# Isolated_Oscilloscope_Diferential_Probe.net
KiCad netlist of a schematic drawn in Altium Designer
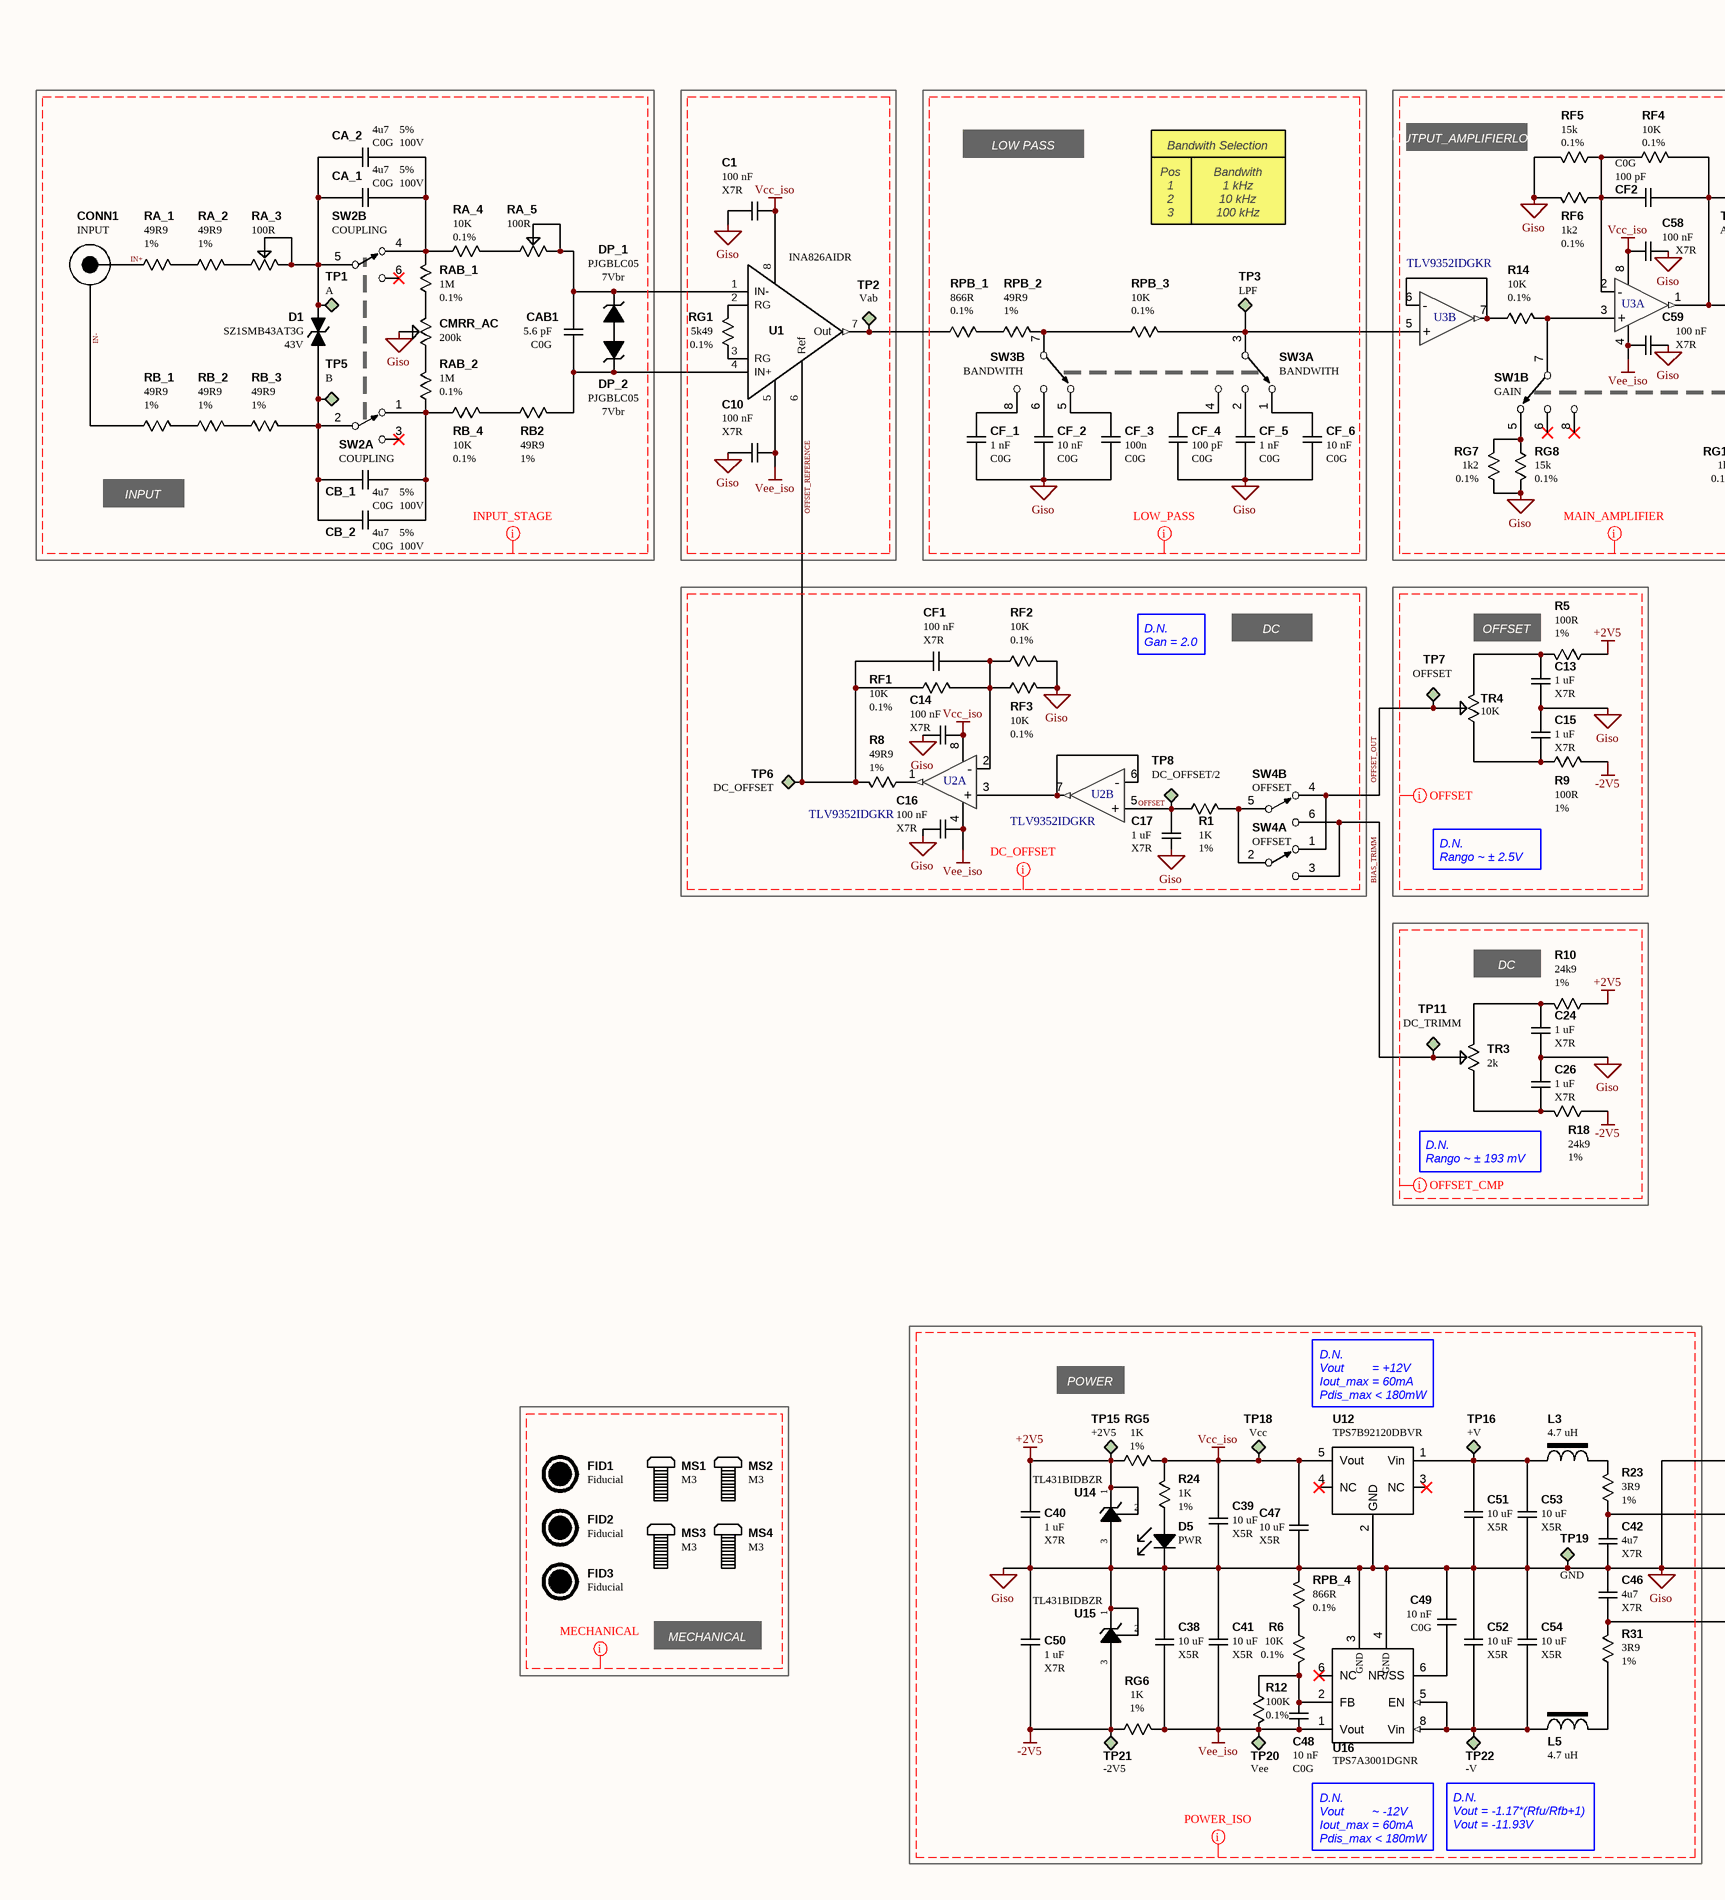
[diagram p0: Isolated_Oscilloscope_Diferential_Probe.SchDoc, left]
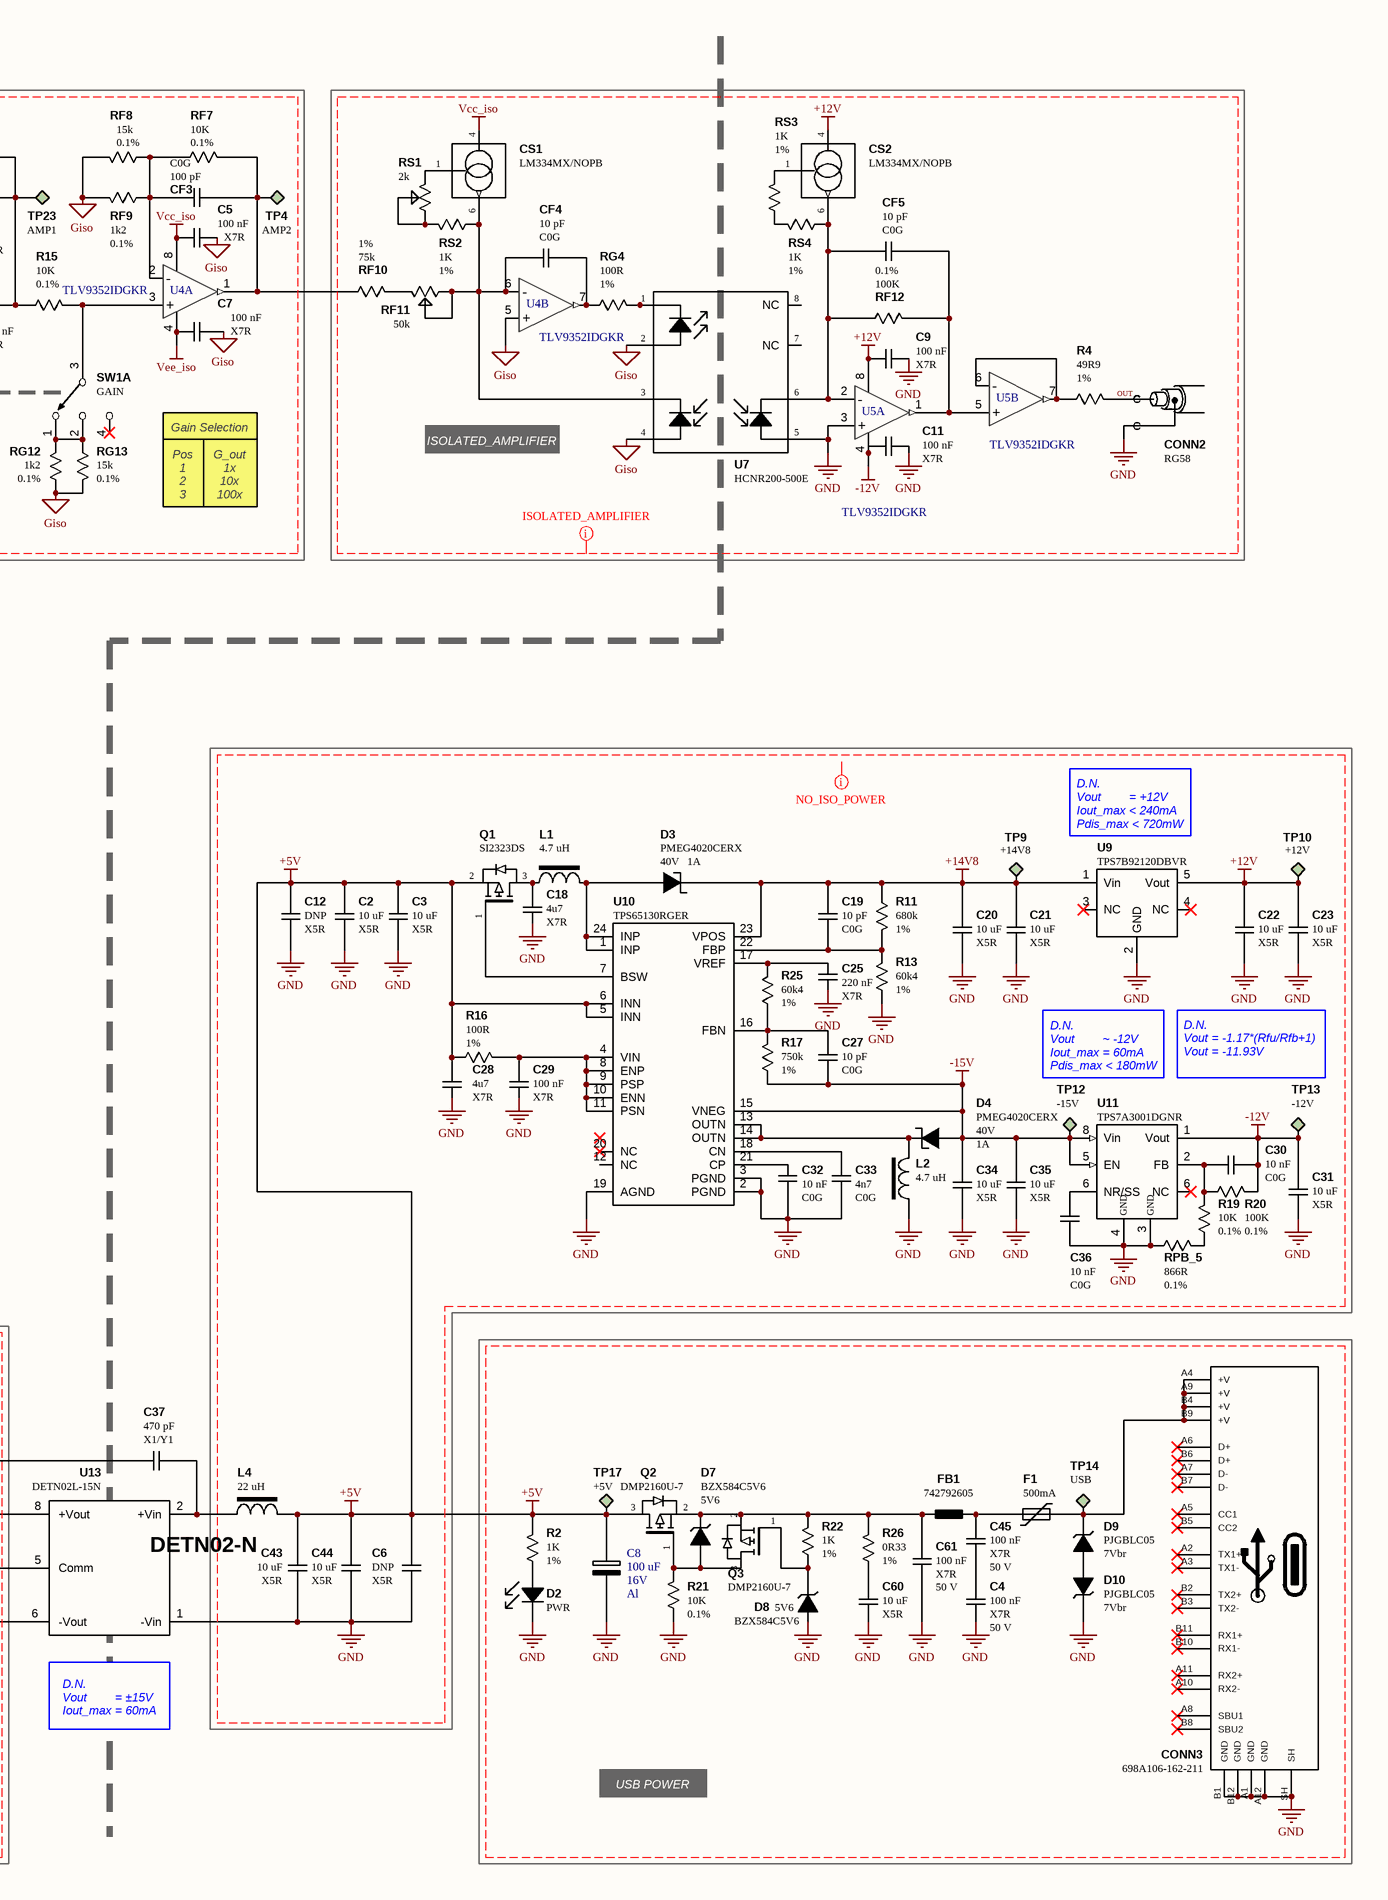
[diagram p1: Isolated_Oscilloscope_Diferential_Probe.SchDoc, right]

(export (version "E")
  (design (tool "Eeschema 10.0.6"))
  (components
    (comp (ref "C1")
      (value "100 nF")
      (footprint "CAP_SMD_0603")
      (description "0.1 µF ±10% 50V Ceramic Capacitor X7R 0603 (1608 Metric)")
      (fields
        (field (name "04_MANUFACTURER PART NUMBER") "CC0603KRX7R9BB104")
        (field (name "05_DIGIKEY PART NUMBER") "311-1344-1-ND")
        (field (name "DIELECTRICO") "X7R")
      )
      (libsource (lib "Libreria_Altium") (part "Capacitor NP"))
    )
    (comp (ref "C2")
      (value "10 uF")
      (footprint "CAP_SMD_0805")
      (description "10 µF ±10% 50V Ceramic Capacitor X5R 0805 (2012 Metric)")
      (fields
        (field (name "04_MANUFACTURER PART NUMBER") "GRM21BR61H106KE43L")
        (field (name "05_DIGIKEY PART NUMBER") "490-18663-1-ND")
        (field (name "DIELECTRICO") "X5R")
      )
      (libsource (lib "Libreria_Altium") (part "Capacitor NP"))
    )
    (comp (ref "C3")
      (value "10 uF")
      (footprint "CAP_SMD_0805")
      (description "10 µF ±10% 50V Ceramic Capacitor X5R 0805 (2012 Metric)")
      (fields
        (field (name "04_MANUFACTURER PART NUMBER") "GRM21BR61H106KE43L")
        (field (name "05_DIGIKEY PART NUMBER") "490-18663-1-ND")
        (field (name "DIELECTRICO") "X5R")
      )
      (libsource (lib "Libreria_Altium") (part "Capacitor NP"))
    )
    (comp (ref "C4")
      (value "100 nF")
      (footprint "CAP_SMD_0603")
      (description "0.1 µF ±10% 50V Ceramic Capacitor X7R 0603 (1608 Metric)")
      (fields
        (field (name "04_MANUFACTURER PART NUMBER") "CC0603KRX7R9BB104")
        (field (name "05_DIGIKEY PART NUMBER") "311-1344-1-ND")
        (field (name "TENSIÓN") "50 V")
        (field (name "DIELECTRICO") "X7R")
      )
      (libsource (lib "Libreria_Altium") (part "Capacitor NP"))
    )
    (comp (ref "C5")
      (value "100 nF")
      (footprint "CAP_SMD_0603")
      (description "0.1 µF ±10% 50V Ceramic Capacitor X7R 0603 (1608 Metric)")
      (fields
        (field (name "04_MANUFACTURER PART NUMBER") "CC0603KRX7R9BB104")
        (field (name "05_DIGIKEY PART NUMBER") "311-1344-1-ND")
        (field (name "DIELECTRICO") "X7R")
      )
      (libsource (lib "Libreria_Altium") (part "Capacitor NP"))
    )
    (comp (ref "C6")
      (value "DNP")
      (footprint "CAP_SMD_0805")
      (description "10 µF ±10% 50V Ceramic Capacitor X5R 0805 (2012 Metric)")
      (fields
        (field (name "04_MANUFACTURER PART NUMBER") "GRM21BR61H106KE43L")
        (field (name "05_DIGIKEY PART NUMBER") "490-18663-1-ND")
        (field (name "DIELECTRICO") "X5R")
      )
      (libsource (lib "Libreria_Altium") (part "Capacitor NP"))
    )
    (comp (ref "C7")
      (value "100 nF")
      (footprint "CAP_SMD_0603")
      (description "0.1 µF ±10% 50V Ceramic Capacitor X7R 0603 (1608 Metric)")
      (fields
        (field (name "04_MANUFACTURER PART NUMBER") "CC0603KRX7R9BB104")
        (field (name "05_DIGIKEY PART NUMBER") "311-1344-1-ND")
        (field (name "DIELECTRICO") "X7R")
      )
      (libsource (lib "Libreria_Altium") (part "Capacitor NP"))
    )
    (comp (ref "C8")
      (value "100 uF")
      (footprint "CAP_SMD_RADIAL_6.3mm")
      (fields
        (field (name "04_MANUFACTURER PART NUMBER") "875105344010")
        (field (name "05_DIGIKEY PART NUMBER") "732-6425-1-ND")
        (field (name "TENSIÓN") "16V")
        (field (name "DIELECTRICO") "Al")
      )
      (libsource (lib "03_Componentes Pasivos") (part "Capacitor Polarizado"))
    )
    (comp (ref "C9")
      (value "100 nF")
      (footprint "CAP_SMD_0603")
      (description "0.1 µF ±10% 50V Ceramic Capacitor X7R 0603 (1608 Metric)")
      (fields
        (field (name "04_MANUFACTURER PART NUMBER") "CC0603KRX7R9BB104")
        (field (name "05_DIGIKEY PART NUMBER") "311-1344-1-ND")
        (field (name "DIELECTRICO") "X7R")
      )
      (libsource (lib "Libreria_Altium") (part "Capacitor NP"))
    )
    (comp (ref "C10")
      (value "100 nF")
      (footprint "CAP_SMD_0603")
      (description "0.1 µF ±10% 50V Ceramic Capacitor X7R 0603 (1608 Metric)")
      (fields
        (field (name "04_MANUFACTURER PART NUMBER") "CC0603KRX7R9BB104")
        (field (name "05_DIGIKEY PART NUMBER") "311-1344-1-ND")
        (field (name "DIELECTRICO") "X7R")
      )
      (libsource (lib "Libreria_Altium") (part "Capacitor NP"))
    )
    (comp (ref "C11")
      (value "100 nF")
      (footprint "CAP_SMD_0603")
      (description "0.1 µF ±10% 50V Ceramic Capacitor X7R 0603 (1608 Metric)")
      (fields
        (field (name "04_MANUFACTURER PART NUMBER") "CC0603KRX7R9BB104")
        (field (name "05_DIGIKEY PART NUMBER") "311-1344-1-ND")
        (field (name "DIELECTRICO") "X7R")
      )
      (libsource (lib "Libreria_Altium") (part "Capacitor NP"))
    )
    (comp (ref "C12")
      (value "DNP")
      (footprint "CAP_SMD_0805")
      (description "10 µF ±10% 50V Ceramic Capacitor X5R 0805 (2012 Metric)")
      (fields
        (field (name "04_MANUFACTURER PART NUMBER") "GRM21BR61H106KE43L")
        (field (name "05_DIGIKEY PART NUMBER") "490-18663-1-ND")
        (field (name "DIELECTRICO") "X5R")
      )
      (libsource (lib "Libreria_Altium") (part "Capacitor NP"))
    )
    (comp (ref "C13")
      (value "1 uF")
      (footprint "CAP_SMD_0805")
      (fields
        (field (name "04_MANUFACTURER PART NUMBER") "CC0805JKX7R9BB105")
        (field (name "05_DIGIKEY PART NUMBER") "311-3498-1-ND")
        (field (name "DIELECTRICO") "X7R")
      )
      (libsource (lib "Libreria_Altium") (part "Capacitor NP"))
    )
    (comp (ref "C14")
      (value "100 nF")
      (footprint "CAP_SMD_0603")
      (description "0.1 µF ±10% 50V Ceramic Capacitor X7R 0603 (1608 Metric)")
      (fields
        (field (name "04_MANUFACTURER PART NUMBER") "CC0603KRX7R9BB104")
        (field (name "05_DIGIKEY PART NUMBER") "311-1344-1-ND")
        (field (name "DIELECTRICO") "X7R")
      )
      (libsource (lib "Libreria_Altium") (part "Capacitor NP"))
    )
    (comp (ref "C15")
      (value "1 uF")
      (footprint "CAP_SMD_0805")
      (fields
        (field (name "04_MANUFACTURER PART NUMBER") "CC0805JKX7R9BB105")
        (field (name "05_DIGIKEY PART NUMBER") "311-3498-1-ND")
        (field (name "DIELECTRICO") "X7R")
      )
      (libsource (lib "Libreria_Altium") (part "Capacitor NP"))
    )
    (comp (ref "C16")
      (value "100 nF")
      (footprint "CAP_SMD_0603")
      (description "0.1 µF ±10% 50V Ceramic Capacitor X7R 0603 (1608 Metric)")
      (fields
        (field (name "04_MANUFACTURER PART NUMBER") "CC0603KRX7R9BB104")
        (field (name "05_DIGIKEY PART NUMBER") "311-1344-1-ND")
        (field (name "DIELECTRICO") "X7R")
      )
      (libsource (lib "Libreria_Altium") (part "Capacitor NP"))
    )
    (comp (ref "C17")
      (value "1 uF")
      (footprint "CAP_SMD_0805")
      (fields
        (field (name "04_MANUFACTURER PART NUMBER") "CC0805JKX7R9BB105")
        (field (name "05_DIGIKEY PART NUMBER") "311-3498-1-ND")
        (field (name "DIELECTRICO") "X7R")
      )
      (libsource (lib "Libreria_Altium") (part "Capacitor NP"))
    )
    (comp (ref "C18")
      (value "4u7")
      (footprint "CAP_SMD_0805")
      (description "4.7 µF ±20% 50V Ceramic Capacitor X7R 0805 (2012 Metric)")
      (fields
        (field (name "04_MANUFACTURER PART NUMBER") "GRM21BZ71H475ME15K")
        (field (name "05_DIGIKEY PART NUMBER") "490-GRM21BZ71H475ME15KCT-ND")
        (field (name "DIELECTRICO") "X7R")
      )
      (libsource (lib "Libreria_Altium") (part "Capacitor NP"))
    )
    (comp (ref "C19")
      (value "10 pF")
      (footprint "CAP_SMD_0603")
      (description "10 pF ±5% 50V Ceramic Capacitor C0G, NP0 0603 (1608 Metric)")
      (fields
        (field (name "04_MANUFACTURER PART NUMBER") "CC0603JRNPO9BN100")
        (field (name "05_DIGIKEY PART NUMBER") "311-1058-1-ND")
        (field (name "DIELECTRICO") "C0G")
      )
      (libsource (lib "Libreria_Altium") (part "Capacitor NP"))
    )
    (comp (ref "C20")
      (value "10 uF")
      (footprint "CAP_SMD_0805")
      (description "10 µF ±10% 50V Ceramic Capacitor X5R 0805 (2012 Metric)")
      (fields
        (field (name "04_MANUFACTURER PART NUMBER") "GRM21BR61H106KE43L")
        (field (name "05_DIGIKEY PART NUMBER") "490-18663-1-ND")
        (field (name "DIELECTRICO") "X5R")
      )
      (libsource (lib "Libreria_Altium") (part "Capacitor NP"))
    )
    (comp (ref "C21")
      (value "10 uF")
      (footprint "CAP_SMD_0805")
      (description "10 µF ±10% 50V Ceramic Capacitor X5R 0805 (2012 Metric)")
      (fields
        (field (name "04_MANUFACTURER PART NUMBER") "GRM21BR61H106KE43L")
        (field (name "05_DIGIKEY PART NUMBER") "490-18663-1-ND")
        (field (name "DIELECTRICO") "X5R")
      )
      (libsource (lib "Libreria_Altium") (part "Capacitor NP"))
    )
    (comp (ref "C22")
      (value "10 uF")
      (footprint "CAP_SMD_0805")
      (description "10 µF ±10% 50V Ceramic Capacitor X5R 0805 (2012 Metric)")
      (fields
        (field (name "04_MANUFACTURER PART NUMBER") "GRM21BR61H106KE43L")
        (field (name "05_DIGIKEY PART NUMBER") "490-18663-1-ND")
        (field (name "DIELECTRICO") "X5R")
      )
      (libsource (lib "Libreria_Altium") (part "Capacitor NP"))
    )
    (comp (ref "C23")
      (value "10 uF")
      (footprint "CAP_SMD_0805")
      (description "10 µF ±10% 50V Ceramic Capacitor X5R 0805 (2012 Metric)")
      (fields
        (field (name "04_MANUFACTURER PART NUMBER") "GRM21BR61H106KE43L")
        (field (name "05_DIGIKEY PART NUMBER") "490-18663-1-ND")
        (field (name "DIELECTRICO") "X5R")
      )
      (libsource (lib "Libreria_Altium") (part "Capacitor NP"))
    )
    (comp (ref "C24")
      (value "1 uF")
      (footprint "CAP_SMD_0805")
      (fields
        (field (name "04_MANUFACTURER PART NUMBER") "CC0805JKX7R9BB105")
        (field (name "05_DIGIKEY PART NUMBER") "311-3498-1-ND")
        (field (name "DIELECTRICO") "X7R")
      )
      (libsource (lib "Libreria_Altium") (part "Capacitor NP"))
    )
    (comp (ref "C25")
      (value "220 nF")
      (footprint "CAP_SMD_0603")
      (description "0.22 µF ±10% 25V Ceramic Capacitor X7R 0603 (1608 Metric)")
      (fields
        (field (name "04_MANUFACTURER PART NUMBER") "CC0603KRX7R8BB224")
        (field (name "05_DIGIKEY PART NUMBER") "311-1803-1-ND")
        (field (name "DIELECTRICO") "X7R")
      )
      (libsource (lib "Libreria_Altium") (part "Capacitor NP"))
    )
    (comp (ref "C26")
      (value "1 uF")
      (footprint "CAP_SMD_0805")
      (fields
        (field (name "04_MANUFACTURER PART NUMBER") "CC0805JKX7R9BB105")
        (field (name "05_DIGIKEY PART NUMBER") "311-3498-1-ND")
        (field (name "DIELECTRICO") "X7R")
      )
      (libsource (lib "Libreria_Altium") (part "Capacitor NP"))
    )
    (comp (ref "C27")
      (value "10 pF")
      (footprint "CAP_SMD_0603")
      (description "10 pF ±5% 50V Ceramic Capacitor C0G, NP0 0603 (1608 Metric)")
      (fields
        (field (name "04_MANUFACTURER PART NUMBER") "CC0603JRNPO9BN100")
        (field (name "05_DIGIKEY PART NUMBER") "311-1058-1-ND")
        (field (name "DIELECTRICO") "C0G")
      )
      (libsource (lib "Libreria_Altium") (part "Capacitor NP"))
    )
    (comp (ref "C28")
      (value "4u7")
      (footprint "CAP_SMD_0805")
      (description "4.7 µF ±20% 50V Ceramic Capacitor X7R 0805 (2012 Metric)")
      (fields
        (field (name "04_MANUFACTURER PART NUMBER") "GRM21BZ71H475ME15K")
        (field (name "05_DIGIKEY PART NUMBER") "490-GRM21BZ71H475ME15KCT-ND")
        (field (name "DIELECTRICO") "X7R")
      )
      (libsource (lib "Libreria_Altium") (part "Capacitor NP"))
    )
    (comp (ref "C29")
      (value "100 nF")
      (footprint "CAP_SMD_0603")
      (description "0.1 µF ±10% 50V Ceramic Capacitor X7R 0603 (1608 Metric)")
      (fields
        (field (name "04_MANUFACTURER PART NUMBER") "CC0603KRX7R9BB104")
        (field (name "05_DIGIKEY PART NUMBER") "311-1344-1-ND")
        (field (name "DIELECTRICO") "X7R")
      )
      (libsource (lib "Libreria_Altium") (part "Capacitor NP"))
    )
    (comp (ref "C30")
      (value "10 nF")
      (footprint "CAP_SMD_0603")
      (description "10000 pF ±5% 50V Ceramic Capacitor C0G, NP0 0603 (1608 Metric)")
      (fields
        (field (name "04_MANUFACTURER PART NUMBER") "GRM1885C1H103JA01D")
        (field (name "05_DIGIKEY PART NUMBER") "490-9666-1-ND")
        (field (name "DIELECTRICO") "C0G")
      )
      (libsource (lib "Libreria_Altium") (part "Capacitor NP"))
    )
    (comp (ref "C31")
      (value "10 uF")
      (footprint "CAP_SMD_0805")
      (description "10 µF ±10% 50V Ceramic Capacitor X5R 0805 (2012 Metric)")
      (fields
        (field (name "04_MANUFACTURER PART NUMBER") "GRM21BR61H106KE43L")
        (field (name "05_DIGIKEY PART NUMBER") "490-18663-1-ND")
        (field (name "DIELECTRICO") "X5R")
      )
      (libsource (lib "Libreria_Altium") (part "Capacitor NP"))
    )
    (comp (ref "C32")
      (value "10 nF")
      (footprint "CAP_SMD_0603")
      (description "10000 pF ±5% 50V Ceramic Capacitor C0G, NP0 0603 (1608 Metric)")
      (fields
        (field (name "04_MANUFACTURER PART NUMBER") "GRM1885C1H103JA01D")
        (field (name "05_DIGIKEY PART NUMBER") "490-9666-1-ND")
        (field (name "DIELECTRICO") "C0G")
      )
      (libsource (lib "Libreria_Altium") (part "Capacitor NP"))
    )
    (comp (ref "C33")
      (value "4n7")
      (footprint "CAP_SMD_0603")
      (description "4700 pF ±1% 50V Ceramic Capacitor C0G, NP0 0603 (1608 Metric)")
      (fields
        (field (name "04_MANUFACTURER PART NUMBER") "CC0603FRNPO9BN472")
        (field (name "05_DIGIKEY PART NUMBER") "13-CC0603FRNPO9BN472CT-ND")
        (field (name "DIELECTRICO") "C0G")
      )
      (libsource (lib "Libreria_Altium") (part "Capacitor NP"))
    )
    (comp (ref "C34")
      (value "10 uF")
      (footprint "CAP_SMD_0805")
      (description "10 µF ±10% 50V Ceramic Capacitor X5R 0805 (2012 Metric)")
      (fields
        (field (name "04_MANUFACTURER PART NUMBER") "GRM21BR61H106KE43L")
        (field (name "05_DIGIKEY PART NUMBER") "490-18663-1-ND")
        (field (name "DIELECTRICO") "X5R")
      )
      (libsource (lib "Libreria_Altium") (part "Capacitor NP"))
    )
    (comp (ref "C35")
      (value "10 uF")
      (footprint "CAP_SMD_0805")
      (description "10 µF ±10% 50V Ceramic Capacitor X5R 0805 (2012 Metric)")
      (fields
        (field (name "04_MANUFACTURER PART NUMBER") "GRM21BR61H106KE43L")
        (field (name "05_DIGIKEY PART NUMBER") "490-18663-1-ND")
        (field (name "DIELECTRICO") "X5R")
      )
      (libsource (lib "Libreria_Altium") (part "Capacitor NP"))
    )
    (comp (ref "C36")
      (value "10 nF")
      (footprint "CAP_SMD_0603")
      (description "10000 pF ±5% 50V Ceramic Capacitor C0G, NP0 0603 (1608 Metric)")
      (fields
        (field (name "04_MANUFACTURER PART NUMBER") "GRM1885C1H103JA01D")
        (field (name "05_DIGIKEY PART NUMBER") "490-9666-1-ND")
        (field (name "DIELECTRICO") "C0G")
      )
      (libsource (lib "Libreria_Altium") (part "Capacitor NP"))
    )
    (comp (ref "C37")
      (value "470 pF")
      (footprint "Capacitor_Disco_7mm")
      (description "470 pF ±10% 1500V (1.5kV) Ceramic Capacitor B Radial, Disc")
      (fields
        (field (name "04_MANUFACTURER PART NUMBER") "DE1B3RA471KN4AP01F")
        (field (name "05_DIGIKEY PART NUMBER") "490-16186-1-ND")
        (field (name "DIELECTRICO") "X1/Y1")
      )
      (libsource (lib "Libreria_Altium") (part "Capacitor NP"))
    )
    (comp (ref "C38")
      (value "10 uF")
      (footprint "CAP_SMD_0805")
      (description "10 µF ±10% 50V Ceramic Capacitor X5R 0805 (2012 Metric)")
      (fields
        (field (name "04_MANUFACTURER PART NUMBER") "GRM21BR61H106KE43L")
        (field (name "05_DIGIKEY PART NUMBER") "490-18663-1-ND")
        (field (name "DIELECTRICO") "X5R")
      )
      (libsource (lib "Libreria_Altium") (part "Capacitor NP"))
    )
    (comp (ref "C39")
      (value "10 uF")
      (footprint "CAP_SMD_0805")
      (description "10 µF ±10% 50V Ceramic Capacitor X5R 0805 (2012 Metric)")
      (fields
        (field (name "04_MANUFACTURER PART NUMBER") "GRM21BR61H106KE43L")
        (field (name "05_DIGIKEY PART NUMBER") "490-18663-1-ND")
        (field (name "DIELECTRICO") "X5R")
      )
      (libsource (lib "Libreria_Altium") (part "Capacitor NP"))
    )
    (comp (ref "C40")
      (value "1 uF")
      (footprint "CAP_SMD_0805")
      (fields
        (field (name "04_MANUFACTURER PART NUMBER") "CC0805JKX7R9BB105")
        (field (name "05_DIGIKEY PART NUMBER") "311-3498-1-ND")
        (field (name "DIELECTRICO") "X7R")
      )
      (libsource (lib "Libreria_Altium") (part "Capacitor NP"))
    )
    (comp (ref "C41")
      (value "10 uF")
      (footprint "CAP_SMD_0805")
      (description "10 µF ±10% 50V Ceramic Capacitor X5R 0805 (2012 Metric)")
      (fields
        (field (name "04_MANUFACTURER PART NUMBER") "GRM21BR61H106KE43L")
        (field (name "05_DIGIKEY PART NUMBER") "490-18663-1-ND")
        (field (name "DIELECTRICO") "X5R")
      )
      (libsource (lib "Libreria_Altium") (part "Capacitor NP"))
    )
    (comp (ref "C42")
      (value "4u7")
      (footprint "CAP_SMD_0805")
      (description "4.7 µF ±20% 50V Ceramic Capacitor X7R 0805 (2012 Metric)")
      (fields
        (field (name "04_MANUFACTURER PART NUMBER") "GRM21BZ71H475ME15K")
        (field (name "05_DIGIKEY PART NUMBER") "490-GRM21BZ71H475ME15KCT-ND")
        (field (name "DIELECTRICO") "X7R")
      )
      (libsource (lib "Libreria_Altium") (part "Capacitor NP"))
    )
    (comp (ref "C43")
      (value "10 uF")
      (footprint "CAP_SMD_0805")
      (description "10 µF ±10% 50V Ceramic Capacitor X5R 0805 (2012 Metric)")
      (fields
        (field (name "04_MANUFACTURER PART NUMBER") "GRM21BR61H106KE43L")
        (field (name "05_DIGIKEY PART NUMBER") "490-18663-1-ND")
        (field (name "DIELECTRICO") "X5R")
      )
      (libsource (lib "Libreria_Altium") (part "Capacitor NP"))
    )
    (comp (ref "C44")
      (value "10 uF")
      (footprint "CAP_SMD_0805")
      (description "10 µF ±10% 50V Ceramic Capacitor X5R 0805 (2012 Metric)")
      (fields
        (field (name "04_MANUFACTURER PART NUMBER") "GRM21BR61H106KE43L")
        (field (name "05_DIGIKEY PART NUMBER") "490-18663-1-ND")
        (field (name "DIELECTRICO") "X5R")
      )
      (libsource (lib "Libreria_Altium") (part "Capacitor NP"))
    )
    (comp (ref "C45")
      (value "100 nF")
      (footprint "CAP_SMD_0603")
      (description "0.1 µF ±10% 50V Ceramic Capacitor X7R 0603 (1608 Metric)")
      (fields
        (field (name "04_MANUFACTURER PART NUMBER") "CC0603KRX7R9BB104")
        (field (name "05_DIGIKEY PART NUMBER") "311-1344-1-ND")
        (field (name "TENSIÓN") "50 V")
        (field (name "DIELECTRICO") "X7R")
      )
      (libsource (lib "Libreria_Altium") (part "Capacitor NP"))
    )
    (comp (ref "C46")
      (value "4u7")
      (footprint "CAP_SMD_0805")
      (description "4.7 µF ±20% 50V Ceramic Capacitor X7R 0805 (2012 Metric)")
      (fields
        (field (name "04_MANUFACTURER PART NUMBER") "GRM21BZ71H475ME15K")
        (field (name "05_DIGIKEY PART NUMBER") "490-GRM21BZ71H475ME15KCT-ND")
        (field (name "DIELECTRICO") "X7R")
      )
      (libsource (lib "Libreria_Altium") (part "Capacitor NP"))
    )
    (comp (ref "C47")
      (value "10 uF")
      (footprint "CAP_SMD_0805")
      (description "10 µF ±10% 50V Ceramic Capacitor X5R 0805 (2012 Metric)")
      (fields
        (field (name "04_MANUFACTURER PART NUMBER") "GRM21BR61H106KE43L")
        (field (name "05_DIGIKEY PART NUMBER") "490-18663-1-ND")
        (field (name "DIELECTRICO") "X5R")
      )
      (libsource (lib "Libreria_Altium") (part "Capacitor NP"))
    )
    (comp (ref "C48")
      (value "10 nF")
      (footprint "CAP_SMD_0603")
      (description "10000 pF ±5% 50V Ceramic Capacitor C0G, NP0 0603 (1608 Metric)")
      (fields
        (field (name "04_MANUFACTURER PART NUMBER") "GRM1885C1H103JA01D")
        (field (name "05_DIGIKEY PART NUMBER") "490-9666-1-ND")
        (field (name "DIELECTRICO") "C0G")
      )
      (libsource (lib "Libreria_Altium") (part "Capacitor NP"))
    )
    (comp (ref "C49")
      (value "10 nF")
      (footprint "CAP_SMD_0603")
      (description "10000 pF ±5% 50V Ceramic Capacitor C0G, NP0 0603 (1608 Metric)")
      (fields
        (field (name "04_MANUFACTURER PART NUMBER") "GRM1885C1H103JA01D")
        (field (name "05_DIGIKEY PART NUMBER") "490-9666-1-ND")
        (field (name "DIELECTRICO") "C0G")
      )
      (libsource (lib "Libreria_Altium") (part "Capacitor NP"))
    )
    (comp (ref "C50")
      (value "1 uF")
      (footprint "CAP_SMD_0805")
      (fields
        (field (name "04_MANUFACTURER PART NUMBER") "CC0805JKX7R9BB105")
        (field (name "05_DIGIKEY PART NUMBER") "311-3498-1-ND")
        (field (name "DIELECTRICO") "X7R")
      )
      (libsource (lib "Libreria_Altium") (part "Capacitor NP"))
    )
    (comp (ref "C51")
      (value "10 uF")
      (footprint "CAP_SMD_0805")
      (description "10 µF ±10% 50V Ceramic Capacitor X5R 0805 (2012 Metric)")
      (fields
        (field (name "04_MANUFACTURER PART NUMBER") "GRM21BR61H106KE43L")
        (field (name "05_DIGIKEY PART NUMBER") "490-18663-1-ND")
        (field (name "DIELECTRICO") "X5R")
      )
      (libsource (lib "Libreria_Altium") (part "Capacitor NP"))
    )
    (comp (ref "C52")
      (value "10 uF")
      (footprint "CAP_SMD_0805")
      (description "10 µF ±10% 50V Ceramic Capacitor X5R 0805 (2012 Metric)")
      (fields
        (field (name "04_MANUFACTURER PART NUMBER") "GRM21BR61H106KE43L")
        (field (name "05_DIGIKEY PART NUMBER") "490-18663-1-ND")
        (field (name "DIELECTRICO") "X5R")
      )
      (libsource (lib "Libreria_Altium") (part "Capacitor NP"))
    )
    (comp (ref "C53")
      (value "10 uF")
      (footprint "CAP_SMD_0805")
      (description "10 µF ±10% 50V Ceramic Capacitor X5R 0805 (2012 Metric)")
      (fields
        (field (name "04_MANUFACTURER PART NUMBER") "GRM21BR61H106KE43L")
        (field (name "05_DIGIKEY PART NUMBER") "490-18663-1-ND")
        (field (name "DIELECTRICO") "X5R")
      )
      (libsource (lib "Libreria_Altium") (part "Capacitor NP"))
    )
    (comp (ref "C54")
      (value "10 uF")
      (footprint "CAP_SMD_0805")
      (description "10 µF ±10% 50V Ceramic Capacitor X5R 0805 (2012 Metric)")
      (fields
        (field (name "04_MANUFACTURER PART NUMBER") "GRM21BR61H106KE43L")
        (field (name "05_DIGIKEY PART NUMBER") "490-18663-1-ND")
        (field (name "DIELECTRICO") "X5R")
      )
      (libsource (lib "Libreria_Altium") (part "Capacitor NP"))
    )
    (comp (ref "C58")
      (value "100 nF")
      (footprint "CAP_SMD_0603")
      (description "0.1 µF ±10% 50V Ceramic Capacitor X7R 0603 (1608 Metric)")
      (fields
        (field (name "04_MANUFACTURER PART NUMBER") "CC0603KRX7R9BB104")
        (field (name "05_DIGIKEY PART NUMBER") "311-1344-1-ND")
        (field (name "DIELECTRICO") "X7R")
      )
      (libsource (lib "Libreria_Altium") (part "Capacitor NP"))
    )
    (comp (ref "C59")
      (value "100 nF")
      (footprint "CAP_SMD_0603")
      (description "0.1 µF ±10% 50V Ceramic Capacitor X7R 0603 (1608 Metric)")
      (fields
        (field (name "04_MANUFACTURER PART NUMBER") "CC0603KRX7R9BB104")
        (field (name "05_DIGIKEY PART NUMBER") "311-1344-1-ND")
        (field (name "DIELECTRICO") "X7R")
      )
      (libsource (lib "Libreria_Altium") (part "Capacitor NP"))
    )
    (comp (ref "C60")
      (value "10 uF")
      (footprint "CAP_SMD_0805")
      (description "10 µF ±10% 50V Ceramic Capacitor X5R 0805 (2012 Metric)")
      (fields
        (field (name "04_MANUFACTURER PART NUMBER") "GRM21BR61H106KE43L")
        (field (name "05_DIGIKEY PART NUMBER") "490-18663-1-ND")
        (field (name "DIELECTRICO") "X5R")
      )
      (libsource (lib "Libreria_Altium") (part "Capacitor NP"))
    )
    (comp (ref "C61")
      (value "100 nF")
      (footprint "CAP_SMD_0603")
      (description "0.1 µF ±10% 50V Ceramic Capacitor X7R 0603 (1608 Metric)")
      (fields
        (field (name "04_MANUFACTURER PART NUMBER") "CC0603KRX7R9BB104")
        (field (name "05_DIGIKEY PART NUMBER") "311-1344-1-ND")
        (field (name "TENSIÓN") "50 V")
        (field (name "DIELECTRICO") "X7R")
      )
      (libsource (lib "Libreria_Altium") (part "Capacitor NP"))
    )
    (comp (ref "CAB1")
      (value "5.6 pF")
      (footprint "CAP_SMD_0603")
      (description "5.6 pF ±0.5pF 50V Ceramic Capacitor C0G, NP0 0603 (1608 Metric)")
      (fields
        (field (name "04_MANUFACTURER PART NUMBER") "CC0603DRNPO9BN5R6")
        (field (name "05_DIGIKEY PART NUMBER") "311-3872-1-ND")
        (field (name "DIELECTRICO") "C0G")
      )
      (libsource (lib "Libreria_Altium") (part "Capacitor NP"))
    )
    (comp (ref "CA_1")
      (value "4u7")
      (footprint "Capacitor_Poliester_15.0mm")
      (description "-55℃~+105℃ 100V 4.7uF Metallized Polyester ±5% 插件,P=15mm Film Capacitors ROHS")
      (fields
        (field (name "04_MANUFACTURER PART NUMBER") "C232A475J6SC000")
        (field (name "05_DIGIKEY PART NUMBER") "NE")
        (field (name "TOLERANCIA") "5%")
        (field (name "TENSIÓN") "100V")
        (field (name "DIELECTRICO") "C0G")
      )
      (libsource (lib "Libreria_Altium") (part "Capacitor NP"))
    )
    (comp (ref "CA_2")
      (value "4u7")
      (footprint "Capacitor_Poliester_15.0mm")
      (description "-55℃~+105℃ 100V 4.7uF Metallized Polyester ±5% 插件,P=15mm Film Capacitors ROHS")
      (fields
        (field (name "04_MANUFACTURER PART NUMBER") "C232A475J6SC000")
        (field (name "05_DIGIKEY PART NUMBER") "NE")
        (field (name "TOLERANCIA") "5%")
        (field (name "TENSIÓN") "100V")
        (field (name "DIELECTRICO") "C0G")
      )
      (libsource (lib "Libreria_Altium") (part "Capacitor NP"))
    )
    (comp (ref "CB_1")
      (value "4u7")
      (footprint "Capacitor_Poliester_15.0mm")
      (description "-55℃~+105℃ 100V 4.7uF Metallized Polyester ±5% 插件,P=15mm Film Capacitors ROHS")
      (fields
        (field (name "04_MANUFACTURER PART NUMBER") "C232A475J6SC000")
        (field (name "05_DIGIKEY PART NUMBER") "NE")
        (field (name "TOLERANCIA") "5%")
        (field (name "TENSIÓN") "100V")
        (field (name "DIELECTRICO") "C0G")
      )
      (libsource (lib "Libreria_Altium") (part "Capacitor NP"))
    )
    (comp (ref "CB_2")
      (value "4u7")
      (footprint "Capacitor_Poliester_15.0mm")
      (description "-55℃~+105℃ 100V 4.7uF Metallized Polyester ±5% 插件,P=15mm Film Capacitors ROHS")
      (fields
        (field (name "04_MANUFACTURER PART NUMBER") "C232A475J6SC000")
        (field (name "05_DIGIKEY PART NUMBER") "NE")
        (field (name "TOLERANCIA") "5%")
        (field (name "TENSIÓN") "100V")
        (field (name "DIELECTRICO") "C0G")
      )
      (libsource (lib "Libreria_Altium") (part "Capacitor NP"))
    )
    (comp (ref "CF1")
      (value "100 nF")
      (footprint "CAP_SMD_0603")
      (description "0.1 µF ±10% 50V Ceramic Capacitor X7R 0603 (1608 Metric)")
      (fields
        (field (name "04_MANUFACTURER PART NUMBER") "CC0603KRX7R9BB104")
        (field (name "05_DIGIKEY PART NUMBER") "311-1344-1-ND")
        (field (name "DIELECTRICO") "X7R")
      )
      (libsource (lib "Libreria_Altium") (part "Capacitor NP"))
    )
    (comp (ref "CF2")
      (value "100 pF")
      (footprint "CAP_SMD_0603")
      (fields
        (field (name "04_MANUFACTURER PART NUMBER") "CC0603GRNPO9BN101")
        (field (name "05_DIGIKEY PART NUMBER") "311-3351-1-ND")
        (field (name "DIELECTRICO") "C0G")
      )
      (libsource (lib "Libreria_Altium") (part "Capacitor NP"))
    )
    (comp (ref "CF3")
      (value "100 pF")
      (footprint "CAP_SMD_0603")
      (fields
        (field (name "04_MANUFACTURER PART NUMBER") "CC0603GRNPO9BN101")
        (field (name "05_DIGIKEY PART NUMBER") "311-3351-1-ND")
        (field (name "DIELECTRICO") "C0G")
      )
      (libsource (lib "Libreria_Altium") (part "Capacitor NP"))
    )
    (comp (ref "CF4")
      (value "10 pF")
      (footprint "CAP_SMD_0603")
      (description "10 pF ±5% 50V Ceramic Capacitor C0G, NP0 0603 (1608 Metric)")
      (fields
        (field (name "04_MANUFACTURER PART NUMBER") "CC0603JRNPO9BN100")
        (field (name "05_DIGIKEY PART NUMBER") "311-1058-1-ND")
        (field (name "DIELECTRICO") "C0G")
      )
      (libsource (lib "Libreria_Altium") (part "Capacitor NP"))
    )
    (comp (ref "CF5")
      (value "10 pF")
      (footprint "CAP_SMD_0603")
      (description "10 pF ±5% 50V Ceramic Capacitor C0G, NP0 0603 (1608 Metric)")
      (fields
        (field (name "04_MANUFACTURER PART NUMBER") "CC0603JRNPO9BN100")
        (field (name "05_DIGIKEY PART NUMBER") "311-1058-1-ND")
        (field (name "DIELECTRICO") "C0G")
      )
      (libsource (lib "Libreria_Altium") (part "Capacitor NP"))
    )
    (comp (ref "CF_1")
      (value "1 nF")
      (footprint "CAP_SMD_0603")
      (description "1000 pF ±2% 50V Ceramic Capacitor C0G, NP0 0603 (1608 Metric)")
      (fields
        (field (name "04_MANUFACTURER PART NUMBER") "CC0603GRNPO9BN102")
        (field (name "05_DIGIKEY PART NUMBER") "311-3916-1-ND")
        (field (name "DIELECTRICO") "C0G")
      )
      (libsource (lib "Libreria_Altium") (part "Capacitor NP"))
    )
    (comp (ref "CF_2")
      (value "10 nF")
      (footprint "CAP_SMD_0603")
      (description "10000 pF ±5% 50V Ceramic Capacitor C0G, NP0 0603 (1608 Metric)")
      (fields
        (field (name "04_MANUFACTURER PART NUMBER") "GRM1885C1H103JA01D")
        (field (name "05_DIGIKEY PART NUMBER") "490-9666-1-ND")
        (field (name "DIELECTRICO") "C0G")
      )
      (libsource (lib "Libreria_Altium") (part "Capacitor NP"))
    )
    (comp (ref "CF_3")
      (value "100n")
      (footprint "CAP_SMD_0603")
      (fields
        (field (name "04_MANUFACTURER PART NUMBER") "CC0603GRNPO9BN101")
        (field (name "05_DIGIKEY PART NUMBER") "311-3351-1-ND")
        (field (name "DIELECTRICO") "C0G")
      )
      (libsource (lib "Libreria_Altium") (part "Capacitor NP"))
    )
    (comp (ref "CF_4")
      (value "100 pF")
      (footprint "CAP_SMD_0603")
      (fields
        (field (name "04_MANUFACTURER PART NUMBER") "CC0603GRNPO9BN101")
        (field (name "05_DIGIKEY PART NUMBER") "311-3351-1-ND")
        (field (name "DIELECTRICO") "C0G")
      )
      (libsource (lib "Libreria_Altium") (part "Capacitor NP"))
    )
    (comp (ref "CF_5")
      (value "1 nF")
      (footprint "CAP_SMD_0603")
      (description "1000 pF ±2% 50V Ceramic Capacitor C0G, NP0 0603 (1608 Metric)")
      (fields
        (field (name "04_MANUFACTURER PART NUMBER") "CC0603GRNPO9BN102")
        (field (name "05_DIGIKEY PART NUMBER") "311-3916-1-ND")
        (field (name "DIELECTRICO") "C0G")
      )
      (libsource (lib "Libreria_Altium") (part "Capacitor NP"))
    )
    (comp (ref "CF_6")
      (value "10 nF")
      (footprint "CAP_SMD_0603")
      (description "10000 pF ±5% 50V Ceramic Capacitor C0G, NP0 0603 (1608 Metric)")
      (fields
        (field (name "04_MANUFACTURER PART NUMBER") "GRM1885C1H103JA01D")
        (field (name "05_DIGIKEY PART NUMBER") "490-9666-1-ND")
        (field (name "DIELECTRICO") "C0G")
      )
      (libsource (lib "Libreria_Altium") (part "Capacitor NP"))
    )
    (comp (ref "CMRR_AC")
      (value "200k")
      (footprint "Trimpot J-Lead")
      (description "200 kOhms 0.125W, 1/8W J Lead Surface Mount Trimmer Potentiometer Cermet 11.0 Turn Top Adjustment")
      (fields
        (field (name "04_MANUFACTURER PART NUMBER") "3223W-1-204E")
        (field (name "05_DIGIKEY PART NUMBER") "3223W-1-204ECT-ND")
      )
      (libsource (lib "Libreria_Altium") (part "Trimpot"))
    )
    (comp (ref "CONN1")
      (value "INPUT")
      (footprint "CONBNC002")
      (description "BNC Connector Jack, Female Socket 50 Ohms Panel Mount, Through Hole, Right Angle Solder")
      (fields
        (field (name "04_MANUFACTURER PART NUMBER") "CONBNC002")
        (field (name "05_DIGIKEY PART NUMBER") "343-CONBNC002-ND")
      )
      (libsource (lib "Libreria_Altium") (part "Conector BNC"))
    )
    (comp (ref "CONN2")
      (value "RG58")
      (footprint "Coaxial_RG58")
      (description "Cable RG58 Soldado directo a PCB")
      (libsource (lib "Libreria_Altium") (part "RG58_Coaxial_Cable"))
    )
    (comp (ref "CONN3")
      (value "698A106-162-211")
      (footprint "1054500101")
      (fields
        (field (name "04_MANUFACTURER PART NUMBER") "1054500101")
        (field (name "05_DIGIKEY PART NUMBER") "WM12856CT-ND")
      )
      (libsource (lib "Libreria_Altium") (part "USB C 3.0"))
    )
    (comp (ref "CS1")
      (value "LM334MX/NOPB")
      (footprint "SOIC_8_IPC")
      (description "Current Source Regulator Adjustable 8-SOIC")
      (fields (field (name "05_DIGIKEY PART NUMBER") "LM334MX/NOPBCT-ND"))
      (libsource (lib "Libreria_Altium") (part "LM334"))
    )
    (comp (ref "CS2")
      (value "LM334MX/NOPB")
      (footprint "SOIC_8_IPC")
      (description "Current Source Regulator Adjustable 8-SOIC")
      (fields (field (name "05_DIGIKEY PART NUMBER") "LM334MX/NOPBCT-ND"))
      (libsource (lib "Libreria_Altium") (part "LM334"))
    )
    (comp (ref "D1")
      (value "SZ1SMB43AT3G")
      (footprint "DO_214AA")
      (description "69.4V Clamp 8.6A Ipp Tvs Diode Surface Mount SMB")
      (fields (field (name "05_DIGIKEY PART NUMBER") "F11563CT-ND") (field (name "TENSIÓN") "43V"))
      (libsource (lib "Libreria_Altium") (part "Diodo TVS Bidireccional"))
    )
    (comp (ref "D2")
      (value "PWR")
      (footprint "LED_0603_1608")
      (description "Diodo LEd")
      (fields
        (field (name "04_MANUFACTURER PART NUMBER") "SML-D12U1WT86")
        (field (name "05_DIGIKEY PART NUMBER") "SML-D12U1WT86CT-ND")
      )
      (libsource (lib "Libreria_Altium") (part "Diodo LED"))
    )
    (comp (ref "D3")
      (value "PMEG4020CERX")
      (footprint "SOD_123W")
      (description "Diode 40 V 2A Surface Mount SOD-123W")
      (fields
        (field (name "05_DIGIKEY PART NUMBER") "1727-PMEG4020CERXCT-ND")
        (field (name "TENSIÓN") "40V")
        (field (name "CORRIENTE") "1A")
      )
      (libsource (lib "Libreria_Altium") (part "Diodo Schottky"))
    )
    (comp (ref "D4")
      (value "PMEG4020CERX")
      (footprint "SOD_123W")
      (description "Diode 40 V 2A Surface Mount SOD-123W")
      (fields
        (field (name "05_DIGIKEY PART NUMBER") "1727-PMEG4020CERXCT-ND")
        (field (name "TENSIÓN") "40V")
        (field (name "CORRIENTE") "1A")
      )
      (libsource (lib "Libreria_Altium") (part "Diodo Schottky"))
    )
    (comp (ref "D5")
      (value "PWR")
      (footprint "LED_0603_1608")
      (description "Diodo LEd")
      (fields
        (field (name "04_MANUFACTURER PART NUMBER") "SML-D12U1WT86")
        (field (name "05_DIGIKEY PART NUMBER") "SML-D12U1WT86CT-ND")
      )
      (libsource (lib "Libreria_Altium") (part "Diodo LED"))
    )
    (comp (ref "D7")
      (value "BZX584C5V6")
      (footprint "SOD_523")
      (description "Diodo Zener")
      (fields
        (field (name "04_MANUFACTURER PART NUMBER") "BZX584C5V6_R1_00001")
        (field (name "05_DIGIKEY PART NUMBER") "3757-BZX584C5V6_R1_00001CT-ND")
        (field (name "TENSIÓN DE TRABAJO") "5V6")
      )
      (libsource (lib "02_Diodos") (part "Diodo Zener"))
    )
    (comp (ref "D8")
      (value "BZX584C5V6")
      (footprint "SOD_523")
      (description "Diodo Zener")
      (fields
        (field (name "04_MANUFACTURER PART NUMBER") "BZX584C5V6_R1_00001")
        (field (name "05_DIGIKEY PART NUMBER") "3757-BZX584C5V6_R1_00001CT-ND")
        (field (name "TENSIÓN DE TRABAJO") "5V6")
      )
      (libsource (lib "02_Diodos") (part "Diodo Zener"))
    )
    (comp (ref "D9")
      (value "PJGBLC05")
      (footprint "SOD_323")
      (description "9.8V Clamp 1A (8/20µs) Ipp Tvs Diode Surface Mount SOD-323")
      (fields
        (field (name "04_MANUFACTURER PART NUMBER") "PJGBLC05_R1_00001")
        (field (name "05_DIGIKEY PART NUMBER") "3757-PJGBLC05_R1_00001CT-ND")
        (field (name "TENSIÓN DE TRABAJO") "7Vbr")
      )
      (libsource (lib "02_Diodos") (part "Diodo TVS Unidireccional"))
    )
    (comp (ref "D10")
      (value "PJGBLC05")
      (footprint "SOD_323")
      (description "9.8V Clamp 1A (8/20µs) Ipp Tvs Diode Surface Mount SOD-323")
      (fields
        (field (name "04_MANUFACTURER PART NUMBER") "PJGBLC05_R1_00001")
        (field (name "05_DIGIKEY PART NUMBER") "3757-PJGBLC05_R1_00001CT-ND")
        (field (name "TENSIÓN DE TRABAJO") "7Vbr")
      )
      (libsource (lib "02_Diodos") (part "Diodo TVS Unidireccional"))
    )
    (comp (ref "DP_1")
      (value "PJGBLC05")
      (footprint "SOD_323")
      (description "9.8V Clamp 1A (8/20µs) Ipp Tvs Diode Surface Mount SOD-323")
      (fields
        (field (name "04_MANUFACTURER PART NUMBER") "PJGBLC05_R1_00001")
        (field (name "05_DIGIKEY PART NUMBER") "3757-PJGBLC05_R1_00001CT-ND")
        (field (name "TENSIÓN DE TRABAJO") "7Vbr")
      )
      (libsource (lib "02_Diodos") (part "Diodo TVS Unidireccional"))
    )
    (comp (ref "DP_2")
      (value "PJGBLC05")
      (footprint "SOD_323")
      (description "9.8V Clamp 1A (8/20µs) Ipp Tvs Diode Surface Mount SOD-323")
      (fields
        (field (name "04_MANUFACTURER PART NUMBER") "PJGBLC05_R1_00001")
        (field (name "05_DIGIKEY PART NUMBER") "3757-PJGBLC05_R1_00001CT-ND")
        (field (name "TENSIÓN DE TRABAJO") "7Vbr")
      )
      (libsource (lib "02_Diodos") (part "Diodo TVS Unidireccional"))
    )
    (comp (ref "F1")
      (value "SMD1206B050TF/15")
      (footprint "RES_SMD_1210")
      (description "Polymeric PTC Resettable Fuse 15V 500 mA Ih Surface Mount 1206 (3216 Metric), Concave")
      (fields
        (field (name "04_MANUFACTURER PART NUMBER") "SMD1206B025TF/24")
        (field (name "05_DIGIKEY PART NUMBER") "13-SMD1206B025TF/24CT-ND")
        (field (name "CORRIENTE") "500mA")
      )
      (libsource (lib "Libreria_Altium") (part "Polyswitch"))
    )
    (comp (ref "FB1")
      (value "742792605")
      (footprint "FERRITE_SMD_0603")
      (fields (field (name "05_DIGIKEY PART NUMBER") "732-4661-1-ND"))
      (libsource (lib "03_Componentes Pasivos") (part "Ferrite Bead"))
    )
    (comp (ref "FID1")
      (value "Fiducial")
      (footprint "Fiducial")
      (description "Fiducial SMD")
      (libsource (lib "Libreria_Altium") (part "Fiducial"))
    )
    (comp (ref "FID2")
      (value "Fiducial")
      (footprint "Fiducial")
      (description "Fiducial SMD")
      (libsource (lib "Libreria_Altium") (part "Fiducial"))
    )
    (comp (ref "FID3")
      (value "Fiducial")
      (footprint "Fiducial")
      (description "Fiducial SMD")
      (libsource (lib "Libreria_Altium") (part "Fiducial"))
    )
    (comp (ref "L1")
      (value "4.7 uH")
      (footprint "IND_DRUM_4.80x4.80mm")
      (description "4.7 µH Shielded Drum Core, Wirewound Inductor 3 A 54mOhm Max Nonstandard")
      (fields
        (field (name "04_MANUFACTURER PART NUMBER") "SRR4828A-4R7Y")
        (field (name "05_DIGIKEY PART NUMBER") "SRR4828A-4R7YCT-ND")
      )
      (libsource (lib "Libreria_Altium") (part "Inductor"))
    )
    (comp (ref "L2")
      (value "4.7 uH")
      (footprint "IND_DRUM_4.80x4.80mm")
      (description "4.7 µH Shielded Drum Core, Wirewound Inductor 3 A 54mOhm Max Nonstandard")
      (fields
        (field (name "04_MANUFACTURER PART NUMBER") "SRR4828A-4R7Y")
        (field (name "05_DIGIKEY PART NUMBER") "SRR4828A-4R7YCT-ND")
      )
      (libsource (lib "") (part "Inductor_1"))
    )
    (comp (ref "L3")
      (value "4.7 uH")
      (footprint "IND_DRUM_4.80x4.80mm")
      (description "4.7 µH Shielded Drum Core, Wirewound Inductor 3 A 54mOhm Max Nonstandard")
      (fields
        (field (name "04_MANUFACTURER PART NUMBER") "SRR4828A-4R7Y")
        (field (name "05_DIGIKEY PART NUMBER") "SRR4828A-4R7YCT-ND")
      )
      (libsource (lib "Libreria_Altium") (part "Inductor"))
    )
    (comp (ref "L4")
      (value "22 uH")
      (footprint "IND_DRUM_5.00x5.00mm")
      (description "22 µH Shielded Drum Core, Wirewound Inductor 1.4 A 152mOhm Max Nonstandard")
      (fields
        (field (name "04_MANUFACTURER PART NUMBER") "SRN5040-220M")
        (field (name "05_DIGIKEY PART NUMBER") "SRN5040-220MCT-ND")
      )
      (libsource (lib "Libreria_Altium") (part "Inductor"))
    )
    (comp (ref "L5")
      (value "4.7 uH")
      (footprint "IND_DRUM_4.80x4.80mm")
      (description "4.7 µH Shielded Drum Core, Wirewound Inductor 3 A 54mOhm Max Nonstandard")
      (fields
        (field (name "04_MANUFACTURER PART NUMBER") "SRR4828A-4R7Y")
        (field (name "05_DIGIKEY PART NUMBER") "SRR4828A-4R7YCT-ND")
      )
      (libsource (lib "Libreria_Altium") (part "Inductor"))
    )
    (comp (ref "MS1")
      (value "M3")
      (footprint "Orificio_M3")
      (description "Tornillo M3")
      (libsource (lib "Libreria_Altium") (part "Tornillo M3"))
    )
    (comp (ref "MS2")
      (value "M3")
      (footprint "Orificio_M3")
      (description "Tornillo M3")
      (libsource (lib "Libreria_Altium") (part "Tornillo M3"))
    )
    (comp (ref "MS3")
      (value "M3")
      (footprint "Orificio_M3")
      (description "Tornillo M3")
      (libsource (lib "Libreria_Altium") (part "Tornillo M3"))
    )
    (comp (ref "MS4")
      (value "M3")
      (footprint "Orificio_M3")
      (description "Tornillo M3")
      (libsource (lib "Libreria_Altium") (part "Tornillo M3"))
    )
    (comp (ref "Q1")
      (value "SI2323DS")
      (footprint "SOT_23-3")
      (description "P-Channel MOSFET SOT-23")
      (fields (field (name "05_DIGIKEY PART NUMBER") "4518-SI2323DSCT-ND"))
      (libsource (lib "Libreria_Altium") (part "PMOS"))
    )
    (comp (ref "Q2")
      (value "DMP2160U-7")
      (footprint "SOT_23-3")
      (description "P-Channel 20 V 3.2A (Ta) 1.4W (Ta) Surface Mount SOT-23-3")
      (fields (field (name "05_DIGIKEY PART NUMBER") "DMP2160UDICT-ND"))
      (libsource (lib "") (part "PMOS_1"))
    )
    (comp (ref "Q3")
      (value "DMP2160U-7")
      (footprint "SOT_23-3")
      (description "P-Channel 20 V 3.2A (Ta) 1.4W (Ta) Surface Mount SOT-23-3")
      (fields (field (name "05_DIGIKEY PART NUMBER") "DMP2160UDICT-ND"))
      (libsource (lib "04_Transistores") (part "PMOS"))
    )
    (comp (ref "R1")
      (value "1K")
      (footprint "RES_SMD_0603")
      (description "1 kOhms ±1% 0.1W, 1/10W Chip Resistor 0603 (1608 Metric) Thin Film")
      (fields
        (field (name "04_MANUFACTURER PART NUMBER") "RT0603FRE131KL")
        (field (name "05_DIGIKEY PART NUMBER") "13-RT0603FRE131KLCT-ND")
        (field (name "TOLERANCIA") "1%")
      )
      (libsource (lib "Libreria_Altium") (part "Resistor"))
    )
    (comp (ref "R2")
      (value "1K")
      (footprint "RES_SMD_0603")
      (description "1 kOhms ±1% 0.1W, 1/10W Chip Resistor 0603 (1608 Metric) Thin Film")
      (fields
        (field (name "04_MANUFACTURER PART NUMBER") "RT0603FRE131KL")
        (field (name "05_DIGIKEY PART NUMBER") "13-RT0603FRE131KLCT-ND")
        (field (name "TOLERANCIA") "1%")
      )
      (libsource (lib "Libreria_Altium") (part "Resistor"))
    )
    (comp (ref "R4")
      (value "49R9")
      (footprint "RES_SMD_0603")
      (description "49.9 Ohms ±1% 0.1W, 1/10W Chip Resistor 0603 (1608 Metric) Thin Film")
      (fields
        (field (name "04_MANUFACTURER PART NUMBER") "RT0603FRD0749R9L")
        (field (name "05_DIGIKEY PART NUMBER") "13-RT0603FRD0749R9LCT-ND")
        (field (name "TOLERANCIA") "1%")
      )
      (libsource (lib "Libreria_Altium") (part "Resistor"))
    )
    (comp (ref "R5")
      (value "100R")
      (footprint "RES_SMD_0603")
      (description "100 Ohms ±1% 0.1W, 1/10W Chip Resistor 0603 (1608 Metric) Thin Film")
      (fields
        (field (name "04_MANUFACTURER PART NUMBER") "RT0603FRE13100RL")
        (field (name "05_DIGIKEY PART NUMBER") "13-RT0603FRE13100RLCT-ND")
        (field (name "TOLERANCIA") "1%")
      )
      (libsource (lib "Libreria_Altium") (part "Resistor"))
    )
    (comp (ref "R6")
      (value "10K")
      (footprint "RES_SMD_0603")
      (description "10 kOhms ±0.1% 0.1W, 1/10W Chip Resistor 0603 (1608 Metric) Thin Film")
      (fields
        (field (name "04_MANUFACTURER PART NUMBER") "RT0603BRD0710KL")
        (field (name "05_DIGIKEY PART NUMBER") "YAG1236CT-ND")
        (field (name "TOLERANCIA") "0.1%")
      )
      (libsource (lib "Libreria_Altium") (part "Resistor"))
    )
    (comp (ref "R8")
      (value "49R9")
      (footprint "RES_SMD_0603")
      (description "49.9 Ohms ±1% 0.1W, 1/10W Chip Resistor 0603 (1608 Metric) Thin Film")
      (fields
        (field (name "04_MANUFACTURER PART NUMBER") "RT0603FRD0749R9L")
        (field (name "05_DIGIKEY PART NUMBER") "13-RT0603FRD0749R9LCT-ND")
        (field (name "TOLERANCIA") "1%")
      )
      (libsource (lib "Libreria_Altium") (part "Resistor"))
    )
    (comp (ref "R9")
      (value "100R")
      (footprint "RES_SMD_0603")
      (description "100 Ohms ±1% 0.1W, 1/10W Chip Resistor 0603 (1608 Metric) Thin Film")
      (fields
        (field (name "04_MANUFACTURER PART NUMBER") "RT0603FRE13100RL")
        (field (name "05_DIGIKEY PART NUMBER") "13-RT0603FRE13100RLCT-ND")
        (field (name "TOLERANCIA") "1%")
      )
      (libsource (lib "Libreria_Altium") (part "Resistor"))
    )
    (comp (ref "R10")
      (value "24k9")
      (footprint "RES_SMD_0603")
      (description "24.9 kOhms ±1% 0.1W, 1/10W Chip Resistor 0603 (1608 Metric) Thick Film")
      (fields
        (field (name "04_MANUFACTURER PART NUMBER") "RC0603FR-1024K9L")
        (field (name "05_DIGIKEY PART NUMBER") "13-RC0603FR-1024K9LCT-ND")
        (field (name "TOLERANCIA") "1%")
      )
      (libsource (lib "Libreria_Altium") (part "Resistor"))
    )
    (comp (ref "R11")
      (value "680k")
      (footprint "RES_SMD_0603")
      (description "680 kOhms ±1% 0.1W, 1/10W Chip Resistor 0603 (1608 Metric) Moisture Resistant Thick Film")
      (fields
        (field (name "04_MANUFACTURER PART NUMBER") "311-680KHRCT-ND")
        (field (name "05_DIGIKEY PART NUMBER") "RC0603FR-07680KL")
        (field (name "TOLERANCIA") "1%")
      )
      (libsource (lib "Libreria_Altium") (part "Resistor"))
    )
    (comp (ref "R12")
      (value "100K")
      (footprint "RES_SMD_0603")
      (description "100 kOhms ±0.1% 0.1W, 1/10W Chip Resistor 0603 (1608 Metric) Thin Film")
      (fields
        (field (name "04_MANUFACTURER PART NUMBER") "RT0603BRD07100KL")
        (field (name "05_DIGIKEY PART NUMBER") "YAG1235CT-ND")
        (field (name "TOLERANCIA") "0.1%")
      )
      (libsource (lib "Libreria_Altium") (part "Resistor"))
    )
    (comp (ref "R13")
      (value "60k4")
      (footprint "RES_SMD_0603")
      (description "60.4 kOhms ±1% 0.1W, 1/10W Chip Resistor 0603 (1608 Metric) Moisture Resistant Thick Film")
      (fields
        (field (name "04_MANUFACTURER PART NUMBER") "RC0603FR-0760K4L")
        (field (name "05_DIGIKEY PART NUMBER") "311-60.4KHRCT-ND")
        (field (name "TOLERANCIA") "1%")
      )
      (libsource (lib "Libreria_Altium") (part "Resistor"))
    )
    (comp (ref "R14")
      (value "10K")
      (footprint "RES_SMD_0603")
      (description "10 kOhms ±0.1% 0.1W, 1/10W Chip Resistor 0603 (1608 Metric) Thin Film")
      (fields
        (field (name "04_MANUFACTURER PART NUMBER") "RT0603BRD0710KL")
        (field (name "05_DIGIKEY PART NUMBER") "YAG1236CT-ND")
        (field (name "TOLERANCIA") "0.1%")
      )
      (libsource (lib "Libreria_Altium") (part "Resistor"))
    )
    (comp (ref "R15")
      (value "10K")
      (footprint "RES_SMD_0603")
      (description "10 kOhms ±0.1% 0.1W, 1/10W Chip Resistor 0603 (1608 Metric) Thin Film")
      (fields
        (field (name "04_MANUFACTURER PART NUMBER") "RT0603BRD0710KL")
        (field (name "05_DIGIKEY PART NUMBER") "YAG1236CT-ND")
        (field (name "TOLERANCIA") "0.1%")
      )
      (libsource (lib "Libreria_Altium") (part "Resistor"))
    )
    (comp (ref "R16")
      (value "100R")
      (footprint "RES_SMD_0603")
      (description "100 Ohms ±1% 0.1W, 1/10W Chip Resistor 0603 (1608 Metric) Thin Film")
      (fields
        (field (name "04_MANUFACTURER PART NUMBER") "RT0603FRE13100RL")
        (field (name "05_DIGIKEY PART NUMBER") "13-RT0603FRE13100RLCT-ND")
        (field (name "TOLERANCIA") "1%")
      )
      (libsource (lib "Libreria_Altium") (part "Resistor"))
    )
    (comp (ref "R17")
      (value "750k")
      (footprint "RES_SMD_0603")
      (description "750 kOhms ±1% 0.1W, 1/10W Chip Resistor 0603 (1608 Metric) Moisture Resistant Thick Film")
      (fields
        (field (name "04_MANUFACTURER PART NUMBER") "RC0603FR-07750KL")
        (field (name "05_DIGIKEY PART NUMBER") "311-750KHRCT-ND")
        (field (name "TOLERANCIA") "1%")
      )
      (libsource (lib "Libreria_Altium") (part "Resistor"))
    )
    (comp (ref "R18")
      (value "24k9")
      (footprint "RES_SMD_0603")
      (description "24.9 kOhms ±1% 0.1W, 1/10W Chip Resistor 0603 (1608 Metric) Thick Film")
      (fields
        (field (name "04_MANUFACTURER PART NUMBER") "RC0603FR-1024K9L")
        (field (name "05_DIGIKEY PART NUMBER") "13-RC0603FR-1024K9LCT-ND")
        (field (name "TOLERANCIA") "1%")
      )
      (libsource (lib "Libreria_Altium") (part "Resistor"))
    )
    (comp (ref "R19")
      (value "10K")
      (footprint "RES_SMD_0603")
      (description "10 kOhms ±0.1% 0.1W, 1/10W Chip Resistor 0603 (1608 Metric) Thin Film")
      (fields
        (field (name "04_MANUFACTURER PART NUMBER") "RT0603BRD0710KL")
        (field (name "05_DIGIKEY PART NUMBER") "YAG1236CT-ND")
        (field (name "TOLERANCIA") "0.1%")
      )
      (libsource (lib "Libreria_Altium") (part "Resistor"))
    )
    (comp (ref "R20")
      (value "100K")
      (footprint "RES_SMD_0603")
      (description "100 kOhms ±0.1% 0.1W, 1/10W Chip Resistor 0603 (1608 Metric) Thin Film")
      (fields
        (field (name "04_MANUFACTURER PART NUMBER") "RT0603BRD07100KL")
        (field (name "05_DIGIKEY PART NUMBER") "YAG1235CT-ND")
        (field (name "TOLERANCIA") "0.1%")
      )
      (libsource (lib "Libreria_Altium") (part "Resistor"))
    )
    (comp (ref "R21")
      (value "10K")
      (footprint "RES_SMD_0603")
      (description "10 kOhms ±0.1% 0.1W, 1/10W Chip Resistor 0603 (1608 Metric) Thin Film")
      (fields
        (field (name "04_MANUFACTURER PART NUMBER") "RT0603BRD0710KL")
        (field (name "05_DIGIKEY PART NUMBER") "YAG1236CT-ND")
        (field (name "TOLERANCIA") "0.1%")
      )
      (libsource (lib "Libreria_Altium") (part "Resistor"))
    )
    (comp (ref "R22")
      (value "1K")
      (footprint "RES_SMD_0603")
      (description "1 kOhms ±1% 0.1W, 1/10W Chip Resistor 0603 (1608 Metric) Thin Film")
      (fields
        (field (name "04_MANUFACTURER PART NUMBER") "RT0603FRE131KL")
        (field (name "05_DIGIKEY PART NUMBER") "13-RT0603FRE131KLCT-ND")
        (field (name "TOLERANCIA") "1%")
      )
      (libsource (lib "Libreria_Altium") (part "Resistor"))
    )
    (comp (ref "R23")
      (value "3R9")
      (footprint "RES_SMD_0603")
      (fields
        (field (name "04_MANUFACTURER PART NUMBER") "RT0603FRE073R9L")
        (field (name "05_DIGIKEY PART NUMBER") "13-RT0603FRE073R9LCT-ND")
        (field (name "TOLERANCIA") "1%")
      )
      (libsource (lib "Libreria_Altium") (part "Resistor"))
    )
    (comp (ref "R24")
      (value "1K")
      (footprint "RES_SMD_0603")
      (description "1 kOhms ±1% 0.1W, 1/10W Chip Resistor 0603 (1608 Metric) Thin Film")
      (fields
        (field (name "04_MANUFACTURER PART NUMBER") "RT0603FRE131KL")
        (field (name "05_DIGIKEY PART NUMBER") "13-RT0603FRE131KLCT-ND")
        (field (name "TOLERANCIA") "1%")
      )
      (libsource (lib "Libreria_Altium") (part "Resistor"))
    )
    (comp (ref "R25")
      (value "60k4")
      (footprint "RES_SMD_0603")
      (description "60.4 kOhms ±1% 0.1W, 1/10W Chip Resistor 0603 (1608 Metric) Moisture Resistant Thick Film")
      (fields
        (field (name "04_MANUFACTURER PART NUMBER") "RC0603FR-0760K4L")
        (field (name "05_DIGIKEY PART NUMBER") "311-60.4KHRCT-ND")
        (field (name "TOLERANCIA") "1%")
      )
      (libsource (lib "Libreria_Altium") (part "Resistor"))
    )
    (comp (ref "R26")
      (value "0R33")
      (footprint "RES_SMD_0603")
      (description "330 mOhms ±1% 0.1W, 1/10W Chip Resistor 0603 (1608 Metric) Current Sense Thick Film")
      (fields
        (field (name "04_MANUFACTURER PART NUMBER") "RL0603FR-070R33L")
        (field (name "05_DIGIKEY PART NUMBER") "311-.33QCT-ND")
        (field (name "TOLERANCIA") "1%")
      )
      (libsource (lib "Libreria_Altium") (part "Resistor"))
    )
    (comp (ref "R31")
      (value "3R9")
      (footprint "RES_SMD_0603")
      (fields
        (field (name "04_MANUFACTURER PART NUMBER") "RT0603FRE073R9L")
        (field (name "05_DIGIKEY PART NUMBER") "13-RT0603FRE073R9LCT-ND")
        (field (name "TOLERANCIA") "1%")
      )
      (libsource (lib "Libreria_Altium") (part "Resistor"))
    )
    (comp (ref "RAB_1")
      (value "1M")
      (footprint "RES_SMD_0603")
      (description "1 MOhms ±0.1% 0.1W, 1/10W Chip Resistor 0603 (1608 Metric) Thin Film")
      (fields
        (field (name "04_MANUFACTURER PART NUMBER") "RT0603BRD071ML")
        (field (name "05_DIGIKEY PART NUMBER") "YAG4498CT-ND")
        (field (name "TOLERANCIA") "0.1%")
      )
      (libsource (lib "Libreria_Altium") (part "Resistor"))
    )
    (comp (ref "RAB_2")
      (value "1M")
      (footprint "RES_SMD_0603")
      (description "1 MOhms ±0.1% 0.1W, 1/10W Chip Resistor 0603 (1608 Metric) Thin Film")
      (fields
        (field (name "04_MANUFACTURER PART NUMBER") "RT0603BRD071ML")
        (field (name "05_DIGIKEY PART NUMBER") "YAG4498CT-ND")
        (field (name "TOLERANCIA") "0.1%")
      )
      (libsource (lib "Libreria_Altium") (part "Resistor"))
    )
    (comp (ref "RA_1")
      (value "49R9")
      (footprint "RES_SMD_0603")
      (description "49.9 Ohms ±1% 0.1W, 1/10W Chip Resistor 0603 (1608 Metric) Thin Film")
      (fields
        (field (name "04_MANUFACTURER PART NUMBER") "RT0603FRD0749R9L")
        (field (name "05_DIGIKEY PART NUMBER") "13-RT0603FRD0749R9LCT-ND")
        (field (name "TOLERANCIA") "1%")
      )
      (libsource (lib "Libreria_Altium") (part "Resistor"))
    )
    (comp (ref "RA_2")
      (value "49R9")
      (footprint "RES_SMD_0603")
      (description "49.9 Ohms ±1% 0.1W, 1/10W Chip Resistor 0603 (1608 Metric) Thin Film")
      (fields
        (field (name "04_MANUFACTURER PART NUMBER") "RT0603FRD0749R9L")
        (field (name "05_DIGIKEY PART NUMBER") "13-RT0603FRD0749R9LCT-ND")
        (field (name "TOLERANCIA") "1%")
      )
      (libsource (lib "Libreria_Altium") (part "Resistor"))
    )
    (comp (ref "RA_3")
      (value "100R")
      (footprint "Trimpot J-Lead")
      (description "100 Ohms 0.25W, 1/4W J Lead Surface Mount Trimmer Potentiometer Cermet 11.0 Turn Top Adjustment")
      (fields
        (field (name "04_MANUFACTURER PART NUMBER") "PVG5A101C03R00")
        (field (name "05_DIGIKEY PART NUMBER") "490-2659-1-ND")
      )
      (libsource (lib "Libreria_Altium") (part "Trimpot"))
    )
    (comp (ref "RA_4")
      (value "10K")
      (footprint "RES_SMD_0603")
      (description "10 kOhms ±0.1% 0.1W, 1/10W Chip Resistor 0603 (1608 Metric) Thin Film")
      (fields
        (field (name "04_MANUFACTURER PART NUMBER") "RT0603BRD0710KL")
        (field (name "05_DIGIKEY PART NUMBER") "YAG1236CT-ND")
        (field (name "TOLERANCIA") "0.1%")
      )
      (libsource (lib "Libreria_Altium") (part "Resistor"))
    )
    (comp (ref "RA_5")
      (value "100R")
      (footprint "Trimpot J-Lead")
      (description "100 Ohms 0.25W, 1/4W J Lead Surface Mount Trimmer Potentiometer Cermet 11.0 Turn Top Adjustment")
      (fields
        (field (name "04_MANUFACTURER PART NUMBER") "PVG5A101C03R00")
        (field (name "05_DIGIKEY PART NUMBER") "490-2659-1-ND")
      )
      (libsource (lib "Libreria_Altium") (part "Trimpot"))
    )
    (comp (ref "RB2")
      (value "49R9")
      (footprint "RES_SMD_0603")
      (description "49.9 Ohms ±1% 0.1W, 1/10W Chip Resistor 0603 (1608 Metric) Thin Film")
      (fields
        (field (name "04_MANUFACTURER PART NUMBER") "RT0603FRD0749R9L")
        (field (name "05_DIGIKEY PART NUMBER") "13-RT0603FRD0749R9LCT-ND")
        (field (name "TOLERANCIA") "1%")
      )
      (libsource (lib "Libreria_Altium") (part "Resistor"))
    )
    (comp (ref "RB_1")
      (value "49R9")
      (footprint "RES_SMD_0603")
      (description "49.9 Ohms ±1% 0.1W, 1/10W Chip Resistor 0603 (1608 Metric) Thin Film")
      (fields
        (field (name "04_MANUFACTURER PART NUMBER") "RT0603FRD0749R9L")
        (field (name "05_DIGIKEY PART NUMBER") "13-RT0603FRD0749R9LCT-ND")
        (field (name "TOLERANCIA") "1%")
      )
      (libsource (lib "Libreria_Altium") (part "Resistor"))
    )
    (comp (ref "RB_2")
      (value "49R9")
      (footprint "RES_SMD_0603")
      (description "49.9 Ohms ±1% 0.1W, 1/10W Chip Resistor 0603 (1608 Metric) Thin Film")
      (fields
        (field (name "04_MANUFACTURER PART NUMBER") "RT0603FRD0749R9L")
        (field (name "05_DIGIKEY PART NUMBER") "13-RT0603FRD0749R9LCT-ND")
        (field (name "TOLERANCIA") "1%")
      )
      (libsource (lib "Libreria_Altium") (part "Resistor"))
    )
    (comp (ref "RB_3")
      (value "49R9")
      (footprint "RES_SMD_0603")
      (description "49.9 Ohms ±1% 0.1W, 1/10W Chip Resistor 0603 (1608 Metric) Thin Film")
      (fields
        (field (name "04_MANUFACTURER PART NUMBER") "RT0603FRD0749R9L")
        (field (name "05_DIGIKEY PART NUMBER") "13-RT0603FRD0749R9LCT-ND")
        (field (name "TOLERANCIA") "1%")
      )
      (libsource (lib "Libreria_Altium") (part "Resistor"))
    )
    (comp (ref "RB_4")
      (value "10K")
      (footprint "RES_SMD_0603")
      (description "10 kOhms ±0.1% 0.1W, 1/10W Chip Resistor 0603 (1608 Metric) Thin Film")
      (fields
        (field (name "04_MANUFACTURER PART NUMBER") "RT0603BRD0710KL")
        (field (name "05_DIGIKEY PART NUMBER") "YAG1236CT-ND")
        (field (name "TOLERANCIA") "0.1%")
      )
      (libsource (lib "Libreria_Altium") (part "Resistor"))
    )
    (comp (ref "RF1")
      (value "10K")
      (footprint "RES_SMD_0603")
      (description "10 kOhms ±0.1% 0.1W, 1/10W Chip Resistor 0603 (1608 Metric) Thin Film")
      (fields
        (field (name "04_MANUFACTURER PART NUMBER") "RT0603BRD0710KL")
        (field (name "05_DIGIKEY PART NUMBER") "YAG1236CT-ND")
        (field (name "TOLERANCIA") "0.1%")
      )
      (libsource (lib "Libreria_Altium") (part "Resistor"))
    )
    (comp (ref "RF2")
      (value "10K")
      (footprint "RES_SMD_0603")
      (description "10 kOhms ±0.1% 0.1W, 1/10W Chip Resistor 0603 (1608 Metric) Thin Film")
      (fields
        (field (name "04_MANUFACTURER PART NUMBER") "RT0603BRD0710KL")
        (field (name "05_DIGIKEY PART NUMBER") "YAG1236CT-ND")
        (field (name "TOLERANCIA") "0.1%")
      )
      (libsource (lib "Libreria_Altium") (part "Resistor"))
    )
    (comp (ref "RF3")
      (value "10K")
      (footprint "RES_SMD_0603")
      (description "10 kOhms ±0.1% 0.1W, 1/10W Chip Resistor 0603 (1608 Metric) Thin Film")
      (fields
        (field (name "04_MANUFACTURER PART NUMBER") "RT0603BRD0710KL")
        (field (name "05_DIGIKEY PART NUMBER") "YAG1236CT-ND")
        (field (name "TOLERANCIA") "0.1%")
      )
      (libsource (lib "Libreria_Altium") (part "Resistor"))
    )
    (comp (ref "RF4")
      (value "10K")
      (footprint "RES_SMD_0603")
      (description "10 kOhms ±0.1% 0.1W, 1/10W Chip Resistor 0603 (1608 Metric) Thin Film")
      (fields
        (field (name "04_MANUFACTURER PART NUMBER") "RT0603BRD0710KL")
        (field (name "05_DIGIKEY PART NUMBER") "YAG1236CT-ND")
        (field (name "TOLERANCIA") "0.1%")
      )
      (libsource (lib "Libreria_Altium") (part "Resistor"))
    )
    (comp (ref "RF5")
      (value "15k")
      (footprint "RES_SMD_0603")
      (description "15 kOhms ±0.1% 0.1W, 1/10W Chip Resistor 0603 (1608 Metric) Thin Film")
      (fields
        (field (name "04_MANUFACTURER PART NUMBER") "RT0603BRD0715KL")
        (field (name "05_DIGIKEY PART NUMBER") "YAG1538CT-ND")
        (field (name "TOLERANCIA") "0.1%")
      )
      (libsource (lib "Libreria_Altium") (part "Resistor"))
    )
    (comp (ref "RF6")
      (value "1k2")
      (footprint "RES_SMD_0603")
      (description "1.2 kOhms ±0.1% 0.1W, 1/10W Chip Resistor 0603 (1608 Metric) Thin Film")
      (fields
        (field (name "04_MANUFACTURER PART NUMBER") "RT0603BRD071K2L")
        (field (name "05_DIGIKEY PART NUMBER") "YAG1563CT-ND")
        (field (name "TOLERANCIA") "0.1%")
      )
      (libsource (lib "Libreria_Altium") (part "Resistor"))
    )
    (comp (ref "RF7")
      (value "10K")
      (footprint "RES_SMD_0603")
      (description "10 kOhms ±0.1% 0.1W, 1/10W Chip Resistor 0603 (1608 Metric) Thin Film")
      (fields
        (field (name "04_MANUFACTURER PART NUMBER") "RT0603BRD0710KL")
        (field (name "05_DIGIKEY PART NUMBER") "YAG1236CT-ND")
        (field (name "TOLERANCIA") "0.1%")
      )
      (libsource (lib "Libreria_Altium") (part "Resistor"))
    )
    (comp (ref "RF8")
      (value "15k")
      (footprint "RES_SMD_0603")
      (description "15 kOhms ±0.1% 0.1W, 1/10W Chip Resistor 0603 (1608 Metric) Thin Film")
      (fields
        (field (name "04_MANUFACTURER PART NUMBER") "RT0603BRD0715KL")
        (field (name "05_DIGIKEY PART NUMBER") "YAG1538CT-ND")
        (field (name "TOLERANCIA") "0.1%")
      )
      (libsource (lib "Libreria_Altium") (part "Resistor"))
    )
    (comp (ref "RF9")
      (value "1k2")
      (footprint "RES_SMD_0603")
      (description "1.2 kOhms ±0.1% 0.1W, 1/10W Chip Resistor 0603 (1608 Metric) Thin Film")
      (fields
        (field (name "04_MANUFACTURER PART NUMBER") "RT0603BRD071K2L")
        (field (name "05_DIGIKEY PART NUMBER") "YAG1563CT-ND")
        (field (name "TOLERANCIA") "0.1%")
      )
      (libsource (lib "Libreria_Altium") (part "Resistor"))
    )
    (comp (ref "RF10")
      (value "75k")
      (footprint "RES_SMD_0603")
      (description "75 kOhms ±1% 0.1W, 1/10W Chip Resistor 0603 (1608 Metric) Moisture Resistant Thick Film")
      (fields
        (field (name "04_MANUFACTURER PART NUMBER") "RC0603FR-0775KL")
        (field (name "05_DIGIKEY PART NUMBER") "311-75.0KHRCT-ND")
        (field (name "TOLERANCIA") "1%")
      )
      (libsource (lib "Libreria_Altium") (part "Resistor"))
    )
    (comp (ref "RF11")
      (value "50k")
      (footprint "Trimpot J-Lead")
      (description "50 kOhms 0.25W, 1/4W J Lead Surface Mount Trimmer Potentiometer Cermet 5.0 Turn Top Adjustment")
      (fields
        (field (name "04_MANUFACTURER PART NUMBER") "3214W-1-503G")
        (field (name "05_DIGIKEY PART NUMBER") "118-3214W-1-503GCT-ND")
      )
      (libsource (lib "Libreria_Altium") (part "Trimpot"))
    )
    (comp (ref "RF12")
      (value "100K")
      (footprint "RES_SMD_0603")
      (description "100 kOhms ±0.1% 0.1W, 1/10W Chip Resistor 0603 (1608 Metric) Thin Film")
      (fields
        (field (name "04_MANUFACTURER PART NUMBER") "RT0603BRD07100KL")
        (field (name "05_DIGIKEY PART NUMBER") "YAG1235CT-ND")
        (field (name "TOLERANCIA") "0.1%")
      )
      (libsource (lib "Libreria_Altium") (part "Resistor"))
    )
    (comp (ref "RG1")
      (value "5k49")
      (footprint "RES_SMD_0603")
      (description "5.49 kOhms ±0.1% 0.1W, 1/10W Chip Resistor 0603 (1608 Metric) Thin Film")
      (fields
        (field (name "04_MANUFACTURER PART NUMBER") "RT0603BRD075K49L")
        (field (name "05_DIGIKEY PART NUMBER") "YAG1698CT-ND")
        (field (name "TOLERANCIA") "0.1%")
      )
      (libsource (lib "Libreria_Altium") (part "Resistor"))
    )
    (comp (ref "RG4")
      (value "100R")
      (footprint "RES_SMD_0603")
      (description "100 Ohms ±1% 0.1W, 1/10W Chip Resistor 0603 (1608 Metric) Thin Film")
      (fields
        (field (name "04_MANUFACTURER PART NUMBER") "RT0603FRE13100RL")
        (field (name "05_DIGIKEY PART NUMBER") "13-RT0603FRE13100RLCT-ND")
        (field (name "TOLERANCIA") "1%")
      )
      (libsource (lib "Libreria_Altium") (part "Resistor"))
    )
    (comp (ref "RG5")
      (value "1K")
      (footprint "RES_SMD_0603")
      (description "1 kOhms ±1% 0.1W, 1/10W Chip Resistor 0603 (1608 Metric) Thin Film")
      (fields
        (field (name "04_MANUFACTURER PART NUMBER") "RT0603FRE131KL")
        (field (name "05_DIGIKEY PART NUMBER") "13-RT0603FRE131KLCT-ND")
        (field (name "TOLERANCIA") "1%")
      )
      (libsource (lib "Libreria_Altium") (part "Resistor"))
    )
    (comp (ref "RG6")
      (value "1K")
      (footprint "RES_SMD_0603")
      (description "1 kOhms ±1% 0.1W, 1/10W Chip Resistor 0603 (1608 Metric) Thin Film")
      (fields
        (field (name "04_MANUFACTURER PART NUMBER") "RT0603FRE131KL")
        (field (name "05_DIGIKEY PART NUMBER") "13-RT0603FRE131KLCT-ND")
        (field (name "TOLERANCIA") "1%")
      )
      (libsource (lib "Libreria_Altium") (part "Resistor"))
    )
    (comp (ref "RG7")
      (value "1k2")
      (footprint "RES_SMD_0603")
      (description "1.2 kOhms ±0.1% 0.1W, 1/10W Chip Resistor 0603 (1608 Metric) Thin Film")
      (fields
        (field (name "04_MANUFACTURER PART NUMBER") "RT0603BRD071K2L")
        (field (name "05_DIGIKEY PART NUMBER") "YAG1563CT-ND")
        (field (name "TOLERANCIA") "0.1%")
      )
      (libsource (lib "Libreria_Altium") (part "Resistor"))
    )
    (comp (ref "RG8")
      (value "15k")
      (footprint "RES_SMD_0603")
      (description "15 kOhms ±0.1% 0.1W, 1/10W Chip Resistor 0603 (1608 Metric) Thin Film")
      (fields
        (field (name "04_MANUFACTURER PART NUMBER") "RT0603BRD0715KL")
        (field (name "05_DIGIKEY PART NUMBER") "YAG1538CT-ND")
        (field (name "TOLERANCIA") "0.1%")
      )
      (libsource (lib "Libreria_Altium") (part "Resistor"))
    )
    (comp (ref "RG12")
      (value "1k2")
      (footprint "RES_SMD_0603")
      (description "1.2 kOhms ±0.1% 0.1W, 1/10W Chip Resistor 0603 (1608 Metric) Thin Film")
      (fields
        (field (name "04_MANUFACTURER PART NUMBER") "RT0603BRD071K2L")
        (field (name "05_DIGIKEY PART NUMBER") "YAG1563CT-ND")
        (field (name "TOLERANCIA") "0.1%")
      )
      (libsource (lib "Libreria_Altium") (part "Resistor"))
    )
    (comp (ref "RG13")
      (value "15k")
      (footprint "RES_SMD_0603")
      (description "15 kOhms ±0.1% 0.1W, 1/10W Chip Resistor 0603 (1608 Metric) Thin Film")
      (fields
        (field (name "04_MANUFACTURER PART NUMBER") "RT0603BRD0715KL")
        (field (name "05_DIGIKEY PART NUMBER") "YAG1538CT-ND")
        (field (name "TOLERANCIA") "0.1%")
      )
      (libsource (lib "Libreria_Altium") (part "Resistor"))
    )
    (comp (ref "RPB_1")
      (value "866R")
      (footprint "RES_SMD_0603")
      (description "866 Ohms ±1% 0.1W, 1/10W Chip Resistor 0603 (1608 Metric) Thin Film")
      (fields
        (field (name "04_MANUFACTURER PART NUMBER") "RT0603BRD07866RL")
        (field (name "05_DIGIKEY PART NUMBER") "YAG1741CT-ND")
        (field (name "TOLERANCIA") "0.1%")
      )
      (libsource (lib "Libreria_Altium") (part "Resistor"))
    )
    (comp (ref "RPB_2")
      (value "49R9")
      (footprint "RES_SMD_0603")
      (description "49.9 Ohms ±1% 0.1W, 1/10W Chip Resistor 0603 (1608 Metric) Thin Film")
      (fields
        (field (name "04_MANUFACTURER PART NUMBER") "RT0603FRD0749R9L")
        (field (name "05_DIGIKEY PART NUMBER") "13-RT0603FRD0749R9LCT-ND")
        (field (name "TOLERANCIA") "1%")
      )
      (libsource (lib "Libreria_Altium") (part "Resistor"))
    )
    (comp (ref "RPB_3")
      (value "10K")
      (footprint "RES_SMD_0603")
      (description "10 kOhms ±0.1% 0.1W, 1/10W Chip Resistor 0603 (1608 Metric) Thin Film")
      (fields
        (field (name "04_MANUFACTURER PART NUMBER") "RT0603BRD0710KL")
        (field (name "05_DIGIKEY PART NUMBER") "YAG1236CT-ND")
        (field (name "TOLERANCIA") "0.1%")
      )
      (libsource (lib "Libreria_Altium") (part "Resistor"))
    )
    (comp (ref "RPB_4")
      (value "866R")
      (footprint "RES_SMD_0603")
      (description "866 Ohms ±1% 0.1W, 1/10W Chip Resistor 0603 (1608 Metric) Thin Film")
      (fields
        (field (name "04_MANUFACTURER PART NUMBER") "RT0603BRD07866RL")
        (field (name "05_DIGIKEY PART NUMBER") "YAG1741CT-ND")
        (field (name "TOLERANCIA") "0.1%")
      )
      (libsource (lib "Libreria_Altium") (part "Resistor"))
    )
    (comp (ref "RPB_5")
      (value "866R")
      (footprint "RES_SMD_0603")
      (description "866 Ohms ±1% 0.1W, 1/10W Chip Resistor 0603 (1608 Metric) Thin Film")
      (fields
        (field (name "04_MANUFACTURER PART NUMBER") "RT0603BRD07866RL")
        (field (name "05_DIGIKEY PART NUMBER") "YAG1741CT-ND")
        (field (name "TOLERANCIA") "0.1%")
      )
      (libsource (lib "Libreria_Altium") (part "Resistor"))
    )
    (comp (ref "RS1")
      (value "2k")
      (footprint "Trimpot J-Lead")
      (description "2 kOhms 0.25W, 1/4W J Lead Surface Mount Trimmer Potentiometer Cermet 5.0 Turn Top Adjustment")
      (fields
        (field (name "04_MANUFACTURER PART NUMBER") "3214W-1-202G")
        (field (name "05_DIGIKEY PART NUMBER") "118-3214W-1-202GCT-ND")
      )
      (libsource (lib "Libreria_Altium") (part "Trimpot"))
    )
    (comp (ref "RS2")
      (value "1K")
      (footprint "RES_SMD_0603")
      (description "1 kOhms ±1% 0.1W, 1/10W Chip Resistor 0603 (1608 Metric) Thin Film")
      (fields
        (field (name "04_MANUFACTURER PART NUMBER") "RT0603FRE131KL")
        (field (name "05_DIGIKEY PART NUMBER") "13-RT0603FRE131KLCT-ND")
        (field (name "TOLERANCIA") "1%")
      )
      (libsource (lib "Libreria_Altium") (part "Resistor"))
    )
    (comp (ref "RS3")
      (value "1K")
      (footprint "RES_SMD_0603")
      (description "1 kOhms ±1% 0.1W, 1/10W Chip Resistor 0603 (1608 Metric) Thin Film")
      (fields
        (field (name "04_MANUFACTURER PART NUMBER") "RT0603FRE131KL")
        (field (name "05_DIGIKEY PART NUMBER") "13-RT0603FRE131KLCT-ND")
        (field (name "TOLERANCIA") "1%")
      )
      (libsource (lib "Libreria_Altium") (part "Resistor"))
    )
    (comp (ref "RS4")
      (value "1K")
      (footprint "RES_SMD_0603")
      (description "1 kOhms ±1% 0.1W, 1/10W Chip Resistor 0603 (1608 Metric) Thin Film")
      (fields
        (field (name "04_MANUFACTURER PART NUMBER") "RT0603FRE131KL")
        (field (name "05_DIGIKEY PART NUMBER") "13-RT0603FRE131KLCT-ND")
        (field (name "TOLERANCIA") "1%")
      )
      (libsource (lib "Libreria_Altium") (part "Resistor"))
    )
    (comp (ref "SW1")
      (value "GAIN")
      (footprint "EG2301B")
      (description "2P3T")
      (fields
        (field (name "04_MANUFACTURER PART NUMBER") "E-Switch")
        (field (name "05_DIGIKEY PART NUMBER") "EG2301B-ND")
      )
      (libsource (lib "05_Interruptores") (part "EG2301B-ND"))
    )
    (comp (ref "SW2")
      (value "COUPLING")
      (footprint "EG2201B")
      (description "Slide Switch DPDT Through Hole")
      (fields
        (field (name "04_MANUFACTURER PART NUMBER") "EG2201B")
        (field (name "05_DIGIKEY PART NUMBER") "EG2201B-ND")
      )
      (libsource (lib "Libreria_Altium") (part "EG2201B"))
    )
    (comp (ref "SW3")
      (value "BANDWITH")
      (footprint "EG2301B")
      (description "2P3T")
      (fields
        (field (name "04_MANUFACTURER PART NUMBER") "E-Switch")
        (field (name "05_DIGIKEY PART NUMBER") "EG2301B-ND")
      )
      (libsource (lib "05_Interruptores") (part "EG2301B-ND"))
    )
    (comp (ref "SW4")
      (value "OFFSET")
      (footprint "EG2201B")
      (description "Slide Switch DPDT Through Hole")
      (fields
        (field (name "04_MANUFACTURER PART NUMBER") "EG2201B")
        (field (name "05_DIGIKEY PART NUMBER") "EG2201B-ND")
      )
      (libsource (lib "Libreria_Altium") (part "EG2201B"))
    )
    (comp (ref "TP1")
      (value "A")
      (footprint "Test_Point_THT")
      (description "Testpoint")
      (fields (field (name "04_MANUFACTURER PART NUMBER") "NA"))
      (libsource (lib "Libreria_Altium") (part "TestPoint_SMD"))
    )
    (comp (ref "TP2")
      (value "Vab")
      (footprint "Test_Point_THT")
      (description "Testpoint")
      (fields (field (name "04_MANUFACTURER PART NUMBER") "NA"))
      (libsource (lib "Libreria_Altium") (part "TestPoint_SMD"))
    )
    (comp (ref "TP3")
      (value "LPF")
      (footprint "Test_Point_THT")
      (description "Testpoint")
      (fields (field (name "04_MANUFACTURER PART NUMBER") "NA"))
      (libsource (lib "Libreria_Altium") (part "TestPoint_SMD"))
    )
    (comp (ref "TP4")
      (value "AMP2")
      (footprint "Test_Point_THT")
      (description "Testpoint")
      (fields (field (name "04_MANUFACTURER PART NUMBER") "NA"))
      (libsource (lib "Libreria_Altium") (part "TestPoint_SMD"))
    )
    (comp (ref "TP5")
      (value "B")
      (footprint "Test_Point_THT")
      (description "Testpoint")
      (fields (field (name "04_MANUFACTURER PART NUMBER") "NA"))
      (libsource (lib "Libreria_Altium") (part "TestPoint_SMD"))
    )
    (comp (ref "TP6")
      (value "DC_OFFSET")
      (footprint "Test_Point_THT")
      (description "Testpoint")
      (fields (field (name "04_MANUFACTURER PART NUMBER") "NA"))
      (libsource (lib "Libreria_Altium") (part "TestPoint_SMD"))
    )
    (comp (ref "TP7")
      (value "OFFSET")
      (footprint "Test_Point_THT")
      (description "Testpoint")
      (fields (field (name "04_MANUFACTURER PART NUMBER") "NA"))
      (libsource (lib "Libreria_Altium") (part "TestPoint_SMD"))
    )
    (comp (ref "TP8")
      (value "DC_OFFSET/2")
      (footprint "Test_Point_THT")
      (description "Testpoint")
      (fields (field (name "04_MANUFACTURER PART NUMBER") "NA"))
      (libsource (lib "Libreria_Altium") (part "TestPoint_SMD"))
    )
    (comp (ref "TP9")
      (value "+14V8")
      (footprint "Test_Point_SMD")
      (description "Testpoint")
      (fields (field (name "04_MANUFACTURER PART NUMBER") "NA"))
      (libsource (lib "Libreria_Altium") (part "TestPoint_SMD"))
    )
    (comp (ref "TP10")
      (value "+12V")
      (footprint "Test_Point_SMD")
      (description "Testpoint")
      (fields (field (name "04_MANUFACTURER PART NUMBER") "NA"))
      (libsource (lib "Libreria_Altium") (part "TestPoint_SMD"))
    )
    (comp (ref "TP11")
      (value "DC_TRIMM")
      (footprint "Test_Point_THT")
      (description "Testpoint")
      (fields (field (name "04_MANUFACTURER PART NUMBER") "NA"))
      (libsource (lib "Libreria_Altium") (part "TestPoint_SMD"))
    )
    (comp (ref "TP12")
      (value "-15V")
      (footprint "Test_Point_SMD")
      (description "Testpoint")
      (fields (field (name "04_MANUFACTURER PART NUMBER") "NA"))
      (libsource (lib "Libreria_Altium") (part "TestPoint_SMD"))
    )
    (comp (ref "TP13")
      (value "-12V")
      (footprint "Test_Point_SMD")
      (description "Testpoint")
      (fields (field (name "04_MANUFACTURER PART NUMBER") "NA"))
      (libsource (lib "Libreria_Altium") (part "TestPoint_SMD"))
    )
    (comp (ref "TP14")
      (value "USB")
      (footprint "Test_Point_THT")
      (description "Testpoint")
      (fields (field (name "04_MANUFACTURER PART NUMBER") "NA"))
      (libsource (lib "Libreria_Altium") (part "TestPoint_SMD"))
    )
    (comp (ref "TP15")
      (value "+2V5")
      (footprint "Test_Point_THT")
      (description "Testpoint")
      (fields (field (name "04_MANUFACTURER PART NUMBER") "NA"))
      (libsource (lib "Libreria_Altium") (part "TestPoint_SMD"))
    )
    (comp (ref "TP16")
      (value "+V")
      (footprint "Test_Point_SMD")
      (description "Testpoint")
      (fields (field (name "04_MANUFACTURER PART NUMBER") "NA"))
      (libsource (lib "Libreria_Altium") (part "TestPoint_SMD"))
    )
    (comp (ref "TP17")
      (value "+5V")
      (footprint "Test_Point_THT")
      (description "Testpoint")
      (fields (field (name "04_MANUFACTURER PART NUMBER") "NA"))
      (libsource (lib "Libreria_Altium") (part "TestPoint_SMD"))
    )
    (comp (ref "TP18")
      (value "Vcc")
      (footprint "Test_Point_THT")
      (description "Testpoint")
      (fields (field (name "04_MANUFACTURER PART NUMBER") "NA"))
      (libsource (lib "Libreria_Altium") (part "TestPoint_SMD"))
    )
    (comp (ref "TP19")
      (value "GND")
      (footprint "Test_Point_SMD")
      (description "Testpoint")
      (fields (field (name "04_MANUFACTURER PART NUMBER") "NA"))
      (libsource (lib "Libreria_Altium") (part "TestPoint_SMD"))
    )
    (comp (ref "TP20")
      (value "Vee")
      (footprint "Test_Point_SMD")
      (description "Testpoint")
      (fields (field (name "04_MANUFACTURER PART NUMBER") "NA"))
      (libsource (lib "Libreria_Altium") (part "TestPoint_SMD"))
    )
    (comp (ref "TP21")
      (value "-2V5")
      (footprint "Test_Point_THT")
      (description "Testpoint")
      (fields (field (name "04_MANUFACTURER PART NUMBER") "NA"))
      (libsource (lib "Libreria_Altium") (part "TestPoint_SMD"))
    )
    (comp (ref "TP22")
      (value "-V")
      (footprint "Test_Point_SMD")
      (description "Testpoint")
      (fields (field (name "04_MANUFACTURER PART NUMBER") "NA"))
      (libsource (lib "Libreria_Altium") (part "TestPoint_SMD"))
    )
    (comp (ref "TP23")
      (value "AMP1")
      (footprint "Test_Point_THT")
      (description "Testpoint")
      (fields (field (name "04_MANUFACTURER PART NUMBER") "NA"))
      (libsource (lib "Libreria_Altium") (part "TestPoint_SMD"))
    )
    (comp (ref "TR3")
      (value "2k")
      (footprint "Trimpot J-Lead")
      (description "2 kOhms 0.25W, 1/4W J Lead Surface Mount Trimmer Potentiometer Cermet 5.0 Turn Top Adjustment")
      (fields
        (field (name "04_MANUFACTURER PART NUMBER") "3214W-1-202G")
        (field (name "05_DIGIKEY PART NUMBER") "118-3214W-1-202GCT-ND")
      )
      (libsource (lib "Libreria_Altium") (part "Trimpot"))
    )
    (comp (ref "TR4")
      (value "10K")
      (footprint "POTENCIOMETRO_RK09K1130081")
      (description "10 kOhms ±0.1% 0.1W, 1/10W Chip Resistor 0603 (1608 Metric) Thin Film")
      (fields
        (field (name "04_MANUFACTURER PART NUMBER") "RT0603BRD0710KL")
        (field (name "05_DIGIKEY PART NUMBER") "YAG1236CT-ND")
      )
      (libsource (lib "Libreria_Altium") (part "Trimpot"))
    )
    (comp (ref "U1")
      (value "INA826AIDR")
      (footprint "SOIC_8_IPC")
      (description "Instrumentation Amplifier 1 Circuit Rail-to-Rail 8-SOIC")
      (fields (field (name "05_DIGIKEY PART NUMBER") "296-30238-1-ND"))
      (libsource (lib "Libreria_Altium") (part "INA826AIDR"))
    )
    (comp (ref "U2")
      (value "TLV9352IDGKR")
      (footprint "VSSOP_8_Standard")
      (description "Standard (General Purpose) Amplifier 2 Circuit Rail-to-Rail 8-VSSOP")
      (fields (field (name "05_DIGIKEY PART NUMBER") "296-TLV9352IDGKRCT-ND"))
      (libsource (lib "01_CI analogicos") (part "Amplificador Operacional Doble"))
    )
    (comp (ref "U3")
      (value "TLV9352IDGKR")
      (footprint "VSSOP_8_Standard")
      (description "Standard (General Purpose) Amplifier 2 Circuit Rail-to-Rail 8-VSSOP")
      (fields (field (name "05_DIGIKEY PART NUMBER") "296-TLV9352IDGKRCT-ND"))
      (libsource (lib "01_CI analogicos") (part "Amplificador Operacional Doble"))
    )
    (comp (ref "U4")
      (value "TLV9352IDGKR")
      (footprint "VSSOP_8_Standard")
      (description "Standard (General Purpose) Amplifier 2 Circuit Rail-to-Rail 8-VSSOP")
      (fields (field (name "05_DIGIKEY PART NUMBER") "296-TLV9352IDGKRCT-ND"))
      (libsource (lib "01_CI analogicos") (part "Amplificador Operacional Doble"))
    )
    (comp (ref "U5")
      (value "TLV9352IDGKR")
      (footprint "VSSOP_8_Standard")
      (description "Standard (General Purpose) Amplifier 2 Circuit Rail-to-Rail 8-VSSOP")
      (fields (field (name "05_DIGIKEY PART NUMBER") "296-TLV9352IDGKRCT-ND"))
      (libsource (lib "01_CI analogicos") (part "Amplificador Operacional Doble"))
    )
    (comp (ref "U7")
      (value "HCNR200-500E")
      (footprint "DIP_8")
      (description "Optoisolator Photovoltaic, Linearized Output 5000Vrms 1 Channel 8-DIP Gull Wing")
      (fields (field (name "05_DIGIKEY PART NUMBER") "516-4038-1-ND"))
      (libsource (lib "Libreria_Altium") (part "HCNR200"))
    )
    (comp (ref "U9")
      (value "TPS7B92120DBVR")
      (footprint "SOT_23-5")
      (description "Linear Voltage Regulator IC Positive Fixed 1 Output 300mA SOT-23-5")
      (fields (field (name "05_DIGIKEY PART NUMBER") "296-TPS7B92120DBVRCT-ND"))
      (libsource (lib "Libreria_Altium") (part "TPS7B92120DBVR"))
    )
    (comp (ref "U10")
      (value "TPS65130RGER")
      (footprint "VFQN_24")
      (fields (field (name "05_DIGIKEY PART NUMBER") "296-17080-1-ND"))
      (libsource (lib "Libreria_Altium") (part "TPS65130RGER"))
    )
    (comp (ref "U11")
      (value "TPS7A3001DGNR")
      (footprint "VSSOP_8")
      (description "Linear Voltage Regulator IC Negative Adjustable 1 Output 200mA 8-HVSSOP")
      (fields (field (name "05_DIGIKEY PART NUMBER") "296-27750-1-ND"))
      (libsource (lib "Libreria_Altium") (part "TPS7A3001DGNR"))
    )
    (comp (ref "U12")
      (value "TPS7B92120DBVR")
      (footprint "SOT_23-5")
      (description "Linear Voltage Regulator IC Positive Fixed 1 Output 300mA SOT-23-5")
      (fields (field (name "05_DIGIKEY PART NUMBER") "296-TPS7B92120DBVRCT-ND"))
      (libsource (lib "") (part "TPS7B92120DBVR_1"))
    )
    (comp (ref "U13")
      (value "DETN02L-15N")
      (footprint "DETN02-N")
      (description "Isolated Module DC DC Converter 2 Output 15V -15V 66mA, 66mA 4.5V - 5.5V Input")
      (fields (field (name "05_DIGIKEY PART NUMBER") "1866-DETN02L-15N-ND"))
      (libsource (lib "Libreria_Altium") (part "DETN02-N"))
    )
    (comp (ref "U14")
      (value "TL431BIDBZR")
      (footprint "SOT_23-3")
      (description "Shunt Voltage Reference IC Adjustable 2.495V 36 VV ±0.5% 100 mA SOT-23-3")
      (fields (field (name "05_DIGIKEY PART NUMBER") "296-18872-1-ND"))
      (libsource (lib "Libreria_Altium") (part "TL431"))
    )
    (comp (ref "U15")
      (value "TL431BIDBZR")
      (footprint "SOT_23-3")
      (description "Shunt Voltage Reference IC Adjustable 2.495V 36 VV ±0.5% 100 mA SOT-23-3")
      (fields (field (name "05_DIGIKEY PART NUMBER") "296-18872-1-ND"))
      (libsource (lib "Libreria_Altium") (part "TL431"))
    )
    (comp (ref "U16")
      (value "TPS7A3001DGNR")
      (footprint "VSSOP_8")
      (description "Linear Voltage Regulator IC Negative Adjustable 1 Output 200mA 8-HVSSOP")
      (fields (field (name "05_DIGIKEY PART NUMBER") "296-27750-1-ND"))
      (libsource (lib "") (part "TPS7A3001DGNR_1"))
    )
  )
  (nets
    (net (code "1") (name "+2V5") (class "Default")
      (node (ref "C40") (pin "2") (pinfunction "2_2") (pintype "passive"))
      (node (ref "R10") (pin "1") (pinfunction "1_1") (pintype "passive"))
      (node (ref "R5") (pin "1") (pinfunction "1_1") (pintype "passive"))
      (node (ref "RG5") (pin "1") (pinfunction "1_1") (pintype "passive"))
      (node (ref "TP15") (pin "1") (pinfunction "1_1") (pintype "passive"))
      (node (ref "U14") (pin "1") (pinfunction "1_1") (pintype "passive"))
      (node (ref "U14") (pin "2") (pinfunction "2_2") (pintype "passive"))
    )
    (net (code "2") (name "+5V") (class "Default")
      (node (ref "C12") (pin "1") (pinfunction "1_1") (pintype "passive"))
      (node (ref "C2") (pin "1") (pinfunction "1_1") (pintype "passive"))
      (node (ref "C28") (pin "2") (pinfunction "2_2") (pintype "passive"))
      (node (ref "C3") (pin "1") (pinfunction "1_1") (pintype "passive"))
      (node (ref "C43") (pin "1") (pinfunction "1_1") (pintype "passive"))
      (node (ref "C44") (pin "1") (pinfunction "1_1") (pintype "passive"))
      (node (ref "C6") (pin "1") (pinfunction "1_1") (pintype "passive"))
      (node (ref "C8") (pin "1") (pinfunction "1_1") (pintype "passive"))
      (node (ref "L4") (pin "1") (pinfunction "1_1") (pintype "passive"))
      (node (ref "Q1") (pin "2") (pinfunction "S_2") (pintype "passive"))
      (node (ref "Q2") (pin "3") (pinfunction "D_3") (pintype "passive"))
      (node (ref "R16") (pin "1") (pinfunction "1_1") (pintype "passive"))
      (node (ref "R2") (pin "2") (pinfunction "2_2") (pintype "passive"))
      (node (ref "TP17") (pin "1") (pinfunction "1_1") (pintype "passive"))
      (node (ref "U10") (pin "5") (pinfunction "INN_5") (pintype "passive"))
      (node (ref "U10") (pin "6") (pinfunction "INN_6") (pintype "passive"))
    )
    (net (code "3") (name "+12V") (class "Default")
      (node (ref "C22") (pin "1") (pinfunction "1_1") (pintype "passive"))
      (node (ref "C23") (pin "1") (pinfunction "1_1") (pintype "passive"))
      (node (ref "C9") (pin "2") (pinfunction "2_2") (pintype "passive"))
      (node (ref "CS2") (pin "4") (pinfunction "Vi+_4") (pintype "power_in"))
      (node (ref "TP10") (pin "1") (pinfunction "1_1") (pintype "passive"))
      (node (ref "U5") (pin "8") (pinfunction "VCC_8") (pintype "power_in"))
      (node (ref "U9") (pin "5") (pinfunction "Vout_5") (pintype "power_in"))
    )
    (net (code "4") (name "+14V8") (class "Default")
      (node (ref "C19") (pin "1") (pinfunction "1_1") (pintype "passive"))
      (node (ref "C20") (pin "1") (pinfunction "1_1") (pintype "passive"))
      (node (ref "C21") (pin "1") (pinfunction "1_1") (pintype "passive"))
      (node (ref "D3") (pin "K") (pinfunction "K_K") (pintype "passive"))
      (node (ref "R11") (pin "1") (pinfunction "1_1") (pintype "passive"))
      (node (ref "TP9") (pin "1") (pinfunction "1_1") (pintype "passive"))
      (node (ref "U10") (pin "23") (pinfunction "VPOS_23") (pintype "passive"))
      (node (ref "U9") (pin "1") (pinfunction "Vin_1") (pintype "passive"))
    )
    (net (code "5") (name "-2V5") (class "Default")
      (node (ref "C50") (pin "1") (pinfunction "1_1") (pintype "passive"))
      (node (ref "R18") (pin "1") (pinfunction "1_1") (pintype "passive"))
      (node (ref "R9") (pin "2") (pinfunction "2_2") (pintype "passive"))
      (node (ref "RG6") (pin "1") (pinfunction "1_1") (pintype "passive"))
      (node (ref "TP21") (pin "1") (pinfunction "1_1") (pintype "passive"))
      (node (ref "U15") (pin "3") (pinfunction "3_3") (pintype "passive"))
    )
    (net (code "6") (name "-12V") (class "Default")
      (node (ref "C11") (pin "2") (pinfunction "2_2") (pintype "passive"))
      (node (ref "C30") (pin "2") (pinfunction "2_2") (pintype "passive"))
      (node (ref "C31") (pin "1") (pinfunction "1_1") (pintype "passive"))
      (node (ref "R20") (pin "2") (pinfunction "2_2") (pintype "passive"))
      (node (ref "TP13") (pin "1") (pinfunction "1_1") (pintype "passive"))
      (node (ref "U11") (pin "1") (pinfunction "Vout_1") (pintype "power_in"))
      (node (ref "U5") (pin "4") (pinfunction "GND_4") (pintype "power_in"))
    )
    (net (code "7") (name "-15V") (class "Default")
      (node (ref "C27") (pin "2") (pinfunction "2_2") (pintype "passive"))
      (node (ref "C34") (pin "1") (pinfunction "1_1") (pintype "passive"))
      (node (ref "C35") (pin "1") (pinfunction "1_1") (pintype "passive"))
      (node (ref "D4") (pin "A") (pinfunction "A_A") (pintype "passive"))
      (node (ref "R17") (pin "1") (pinfunction "1_1") (pintype "passive"))
      (node (ref "TP12") (pin "1") (pinfunction "1_1") (pintype "passive"))
      (node (ref "U10") (pin "15") (pinfunction "VNEG_15") (pintype "passive"))
      (node (ref "U11") (pin "5") (pinfunction "EN_5") (pintype "input"))
      (node (ref "U11") (pin "8") (pinfunction "Vin_8") (pintype "input"))
    )
    (net (code "8") (name "/BIAS_TRIMM") (class "Default")
      (node (ref "SW4") (pin "3") (pinfunction "NO1_3") (pintype "passive"))
      (node (ref "SW4") (pin "6") (pinfunction "NO2_6") (pintype "passive"))
      (node (ref "TP11") (pin "1") (pinfunction "1_1") (pintype "passive"))
      (node (ref "TR3") (pin "3") (pinfunction "3_3") (pintype "passive"))
    )
    (net (code "9") (name "/IN+") (class "Default")
      (node (ref "CONN1") (pin "1") (pinfunction "SIGNAL_1") (pintype "passive"))
      (node (ref "RA_1") (pin "1") (pinfunction "1_1") (pintype "passive"))
    )
    (net (code "10") (name "/IN-") (class "Default")
      (node (ref "CONN1") (pin "2") (pinfunction "2_2") (pintype "passive"))
      (node (ref "RB_1") (pin "1") (pinfunction "1_1") (pintype "passive"))
    )
    (net (code "11") (name "/OFFSET") (class "Default")
      (node (ref "C17") (pin "2") (pinfunction "2_2") (pintype "passive"))
      (node (ref "R1") (pin "1") (pinfunction "1_1") (pintype "passive"))
      (node (ref "TP8") (pin "1") (pinfunction "1_1") (pintype "passive"))
      (node (ref "U2") (pin "5") (pinfunction "+_5") (pintype "passive"))
    )
    (net (code "12") (name "/OFFSET_OUT") (class "Default")
      (node (ref "SW4") (pin "1") (pinfunction "NC1_1") (pintype "passive"))
      (node (ref "SW4") (pin "4") (pinfunction "NC2_4") (pintype "passive"))
      (node (ref "TP7") (pin "1") (pinfunction "1_1") (pintype "passive"))
      (node (ref "TR4") (pin "3") (pinfunction "3_3") (pintype "passive"))
    )
    (net (code "13") (name "/OFFSET_REFERENCE") (class "Default")
      (node (ref "CF1") (pin "1") (pinfunction "1_1") (pintype "passive"))
      (node (ref "R8") (pin "2") (pinfunction "2_2") (pintype "passive"))
      (node (ref "RF1") (pin "1") (pinfunction "1_1") (pintype "passive"))
      (node (ref "TP6") (pin "1") (pinfunction "1_1") (pintype "passive"))
      (node (ref "U1") (pin "6") (pinfunction "Ref_6") (pintype "passive"))
    )
    (net (code "14") (name "/OUT") (class "Default")
      (node (ref "CONN2") (pin "1") (pinfunction "1_1") (pintype "passive"))
      (node (ref "R4") (pin "2") (pinfunction "2_2") (pintype "passive"))
    )
    (net (code "15") (name "GND") (class "Default")
      (node (ref "C11") (pin "1") (pinfunction "1_1") (pintype "passive"))
      (node (ref "C12") (pin "2") (pinfunction "2_2") (pintype "passive"))
      (node (ref "C18") (pin "1") (pinfunction "1_1") (pintype "passive"))
      (node (ref "C2") (pin "2") (pinfunction "2_2") (pintype "passive"))
      (node (ref "C20") (pin "2") (pinfunction "2_2") (pintype "passive"))
      (node (ref "C21") (pin "2") (pinfunction "2_2") (pintype "passive"))
      (node (ref "C22") (pin "2") (pinfunction "2_2") (pintype "passive"))
      (node (ref "C23") (pin "2") (pinfunction "2_2") (pintype "passive"))
      (node (ref "C25") (pin "1") (pinfunction "1_1") (pintype "passive"))
      (node (ref "C28") (pin "1") (pinfunction "1_1") (pintype "passive"))
      (node (ref "C29") (pin "1") (pinfunction "1_1") (pintype "passive"))
      (node (ref "C3") (pin "2") (pinfunction "2_2") (pintype "passive"))
      (node (ref "C31") (pin "2") (pinfunction "2_2") (pintype "passive"))
      (node (ref "C32") (pin "1") (pinfunction "1_1") (pintype "passive"))
      (node (ref "C33") (pin "1") (pinfunction "1_1") (pintype "passive"))
      (node (ref "C34") (pin "2") (pinfunction "2_2") (pintype "passive"))
      (node (ref "C35") (pin "2") (pinfunction "2_2") (pintype "passive"))
      (node (ref "C36") (pin "2") (pinfunction "2_2") (pintype "passive"))
      (node (ref "C4") (pin "1") (pinfunction "1_1") (pintype "passive"))
      (node (ref "C43") (pin "2") (pinfunction "2_2") (pintype "passive"))
      (node (ref "C44") (pin "2") (pinfunction "2_2") (pintype "passive"))
      (node (ref "C6") (pin "2") (pinfunction "2_2") (pintype "passive"))
      (node (ref "C60") (pin "2") (pinfunction "2_2") (pintype "passive"))
      (node (ref "C61") (pin "1") (pinfunction "1_1") (pintype "passive"))
      (node (ref "C8") (pin "2") (pinfunction "2_2") (pintype "passive"))
      (node (ref "C9") (pin "1") (pinfunction "1_1") (pintype "passive"))
      (node (ref "CONN2") (pin "2") (pinfunction "2_2") (pintype "passive"))
      (node (ref "CONN3") (pin "A1") (pinfunction "GND_A1") (pintype "passive"))
      (node (ref "CONN3") (pin "A12") (pinfunction "GND_A12") (pintype "passive"))
      (node (ref "CONN3") (pin "B1") (pinfunction "GND_B1") (pintype "passive"))
      (node (ref "CONN3") (pin "B12") (pinfunction "GND_B12") (pintype "passive"))
      (node (ref "CONN3") (pin "SH") (pinfunction "SH_SH") (pintype "passive"))
      (node (ref "D10") (pin "K") (pinfunction "K_K") (pintype "passive"))
      (node (ref "D2") (pin "K") (pinfunction "K_K") (pintype "passive"))
      (node (ref "D8") (pin "A") (pinfunction "A_A") (pintype "passive"))
      (node (ref "L2") (pin "2") (pinfunction "2_2") (pintype "passive"))
      (node (ref "R13") (pin "1") (pinfunction "1_1") (pintype "passive"))
      (node (ref "R21") (pin "1") (pinfunction "1_1") (pintype "passive"))
      (node (ref "RPB_5") (pin "1") (pinfunction "1_1") (pintype "passive"))
      (node (ref "U10") (pin "19") (pinfunction "AGND_19") (pintype "passive"))
      (node (ref "U10") (pin "2") (pinfunction "PGND_2") (pintype "passive"))
      (node (ref "U10") (pin "3") (pinfunction "PGND_3") (pintype "passive"))
      (node (ref "U11") (pin "3") (pinfunction "GND_3") (pintype "passive"))
      (node (ref "U11") (pin "4") (pinfunction "GND_4") (pintype "passive"))
      (node (ref "U13") (pin "1") (pinfunction "-Vin_1") (pintype "passive"))
      (node (ref "U5") (pin "3") (pinfunction "+_3") (pintype "passive"))
      (node (ref "U7") (pin "5") (pinfunction "PD2+_5") (pintype "passive"))
      (node (ref "U9") (pin "2") (pinfunction "GND_2") (pintype "passive"))
    )
    (net (code "16") (name "Giso") (class "Default")
      (node (ref "C1") (pin "1") (pinfunction "1_1") (pintype "passive"))
      (node (ref "C10") (pin "1") (pinfunction "1_1") (pintype "passive"))
      (node (ref "C13") (pin "1") (pinfunction "1_1") (pintype "passive"))
      (node (ref "C14") (pin "1") (pinfunction "1_1") (pintype "passive"))
      (node (ref "C15") (pin "2") (pinfunction "2_2") (pintype "passive"))
      (node (ref "C16") (pin "1") (pinfunction "1_1") (pintype "passive"))
      (node (ref "C17") (pin "1") (pinfunction "1_1") (pintype "passive"))
      (node (ref "C24") (pin "1") (pinfunction "1_1") (pintype "passive"))
      (node (ref "C26") (pin "2") (pinfunction "2_2") (pintype "passive"))
      (node (ref "C37") (pin "1") (pinfunction "1_1") (pintype "passive"))
      (node (ref "C38") (pin "1") (pinfunction "1_1") (pintype "passive"))
      (node (ref "C39") (pin "2") (pinfunction "2_2") (pintype "passive"))
      (node (ref "C40") (pin "1") (pinfunction "1_1") (pintype "passive"))
      (node (ref "C41") (pin "1") (pinfunction "1_1") (pintype "passive"))
      (node (ref "C42") (pin "1") (pinfunction "1_1") (pintype "passive"))
      (node (ref "C46") (pin "2") (pinfunction "2_2") (pintype "passive"))
      (node (ref "C47") (pin "2") (pinfunction "2_2") (pintype "passive"))
      (node (ref "C49") (pin "1") (pinfunction "1_1") (pintype "passive"))
      (node (ref "C5") (pin "1") (pinfunction "1_1") (pintype "passive"))
      (node (ref "C50") (pin "2") (pinfunction "2_2") (pintype "passive"))
      (node (ref "C51") (pin "2") (pinfunction "2_2") (pintype "passive"))
      (node (ref "C52") (pin "1") (pinfunction "1_1") (pintype "passive"))
      (node (ref "C53") (pin "2") (pinfunction "2_2") (pintype "passive"))
      (node (ref "C54") (pin "1") (pinfunction "1_1") (pintype "passive"))
      (node (ref "C58") (pin "1") (pinfunction "1_1") (pintype "passive"))
      (node (ref "C59") (pin "1") (pinfunction "1_1") (pintype "passive"))
      (node (ref "C7") (pin "1") (pinfunction "1_1") (pintype "passive"))
      (node (ref "CF_1") (pin "1") (pinfunction "1_1") (pintype "passive"))
      (node (ref "CF_2") (pin "1") (pinfunction "1_1") (pintype "passive"))
      (node (ref "CF_3") (pin "1") (pinfunction "1_1") (pintype "passive"))
      (node (ref "CF_4") (pin "1") (pinfunction "1_1") (pintype "passive"))
      (node (ref "CF_5") (pin "1") (pinfunction "1_1") (pintype "passive"))
      (node (ref "CF_6") (pin "1") (pinfunction "1_1") (pintype "passive"))
      (node (ref "CMRR_AC") (pin "3") (pinfunction "3_3") (pintype "passive"))
      (node (ref "D5") (pin "K") (pinfunction "K_K") (pintype "passive"))
      (node (ref "RF2") (pin "2") (pinfunction "2_2") (pintype "passive"))
      (node (ref "RF3") (pin "2") (pinfunction "2_2") (pintype "passive"))
      (node (ref "RF5") (pin "2") (pinfunction "2_2") (pintype "passive"))
      (node (ref "RF6") (pin "2") (pinfunction "2_2") (pintype "passive"))
      (node (ref "RF8") (pin "2") (pinfunction "2_2") (pintype "passive"))
      (node (ref "RF9") (pin "2") (pinfunction "2_2") (pintype "passive"))
      (node (ref "RG12") (pin "1") (pinfunction "1_1") (pintype "passive"))
      (node (ref "RG13") (pin "2") (pinfunction "2_2") (pintype "passive"))
      (node (ref "RG7") (pin "1") (pinfunction "1_1") (pintype "passive"))
      (node (ref "RG8") (pin "2") (pinfunction "2_2") (pintype "passive"))
      (node (ref "RPB_4") (pin "2") (pinfunction "2_2") (pintype "passive"))
      (node (ref "TP19") (pin "1") (pinfunction "1_1") (pintype "passive"))
      (node (ref "U12") (pin "2") (pinfunction "GND_2") (pintype "passive"))
      (node (ref "U13") (pin "5") (pinfunction "Comm_5") (pintype "passive"))
      (node (ref "U14") (pin "3") (pinfunction "3_3") (pintype "passive"))
      (node (ref "U15") (pin "1") (pinfunction "1_1") (pintype "passive"))
      (node (ref "U15") (pin "2") (pinfunction "2_2") (pintype "passive"))
      (node (ref "U16") (pin "3") (pinfunction "GND_3") (pintype "passive"))
      (node (ref "U16") (pin "4") (pinfunction "GND_4") (pintype "passive"))
      (node (ref "U4") (pin "5") (pinfunction "+_5") (pintype "passive"))
      (node (ref "U7") (pin "2") (pinfunction "LED+_2") (pintype "passive"))
      (node (ref "U7") (pin "4") (pinfunction "PD1+_4") (pintype "passive"))
    )
    (net (code "17") (name "Net-(C4-Pad2)") (class "Default")
      (node (ref "C4") (pin "2") (pinfunction "2_2") (pintype "passive"))
      (node (ref "C45") (pin "1") (pinfunction "1_1") (pintype "passive"))
    )
    (net (code "18") (name "Net-(C13-Pad2)") (class "Default")
      (node (ref "C13") (pin "2") (pinfunction "2_2") (pintype "passive"))
      (node (ref "R5") (pin "2") (pinfunction "2_2") (pintype "passive"))
      (node (ref "TR4") (pin "1") (pinfunction "1_1") (pintype "passive"))
    )
    (net (code "19") (name "Net-(C15-Pad1)") (class "Default")
      (node (ref "C15") (pin "1") (pinfunction "1_1") (pintype "passive"))
      (node (ref "R9") (pin "1") (pinfunction "1_1") (pintype "passive"))
      (node (ref "TR4") (pin "2") (pinfunction "2_2") (pintype "passive"))
    )
    (net (code "20") (name "Net-(C24-Pad2)") (class "Default")
      (node (ref "C24") (pin "2") (pinfunction "2_2") (pintype "passive"))
      (node (ref "R10") (pin "2") (pinfunction "2_2") (pintype "passive"))
      (node (ref "TR3") (pin "2") (pinfunction "2_2") (pintype "passive"))
    )
    (net (code "21") (name "Net-(C26-Pad1)") (class "Default")
      (node (ref "C26") (pin "1") (pinfunction "1_1") (pintype "passive"))
      (node (ref "R18") (pin "2") (pinfunction "2_2") (pintype "passive"))
      (node (ref "TR3") (pin "1") (pinfunction "1_1") (pintype "passive"))
    )
    (net (code "22") (name "Net-(C45-Pad2)") (class "Default")
      (node (ref "C45") (pin "2") (pinfunction "2_2") (pintype "passive"))
      (node (ref "F1") (pin "2") (pinfunction "2_2") (pintype "passive"))
      (node (ref "FB1") (pin "2") (pinfunction "2_2") (pintype "passive"))
    )
    (net (code "23") (name "Net-(C60-Pad1)") (class "Default")
      (node (ref "C60") (pin "1") (pinfunction "1_1") (pintype "passive"))
      (node (ref "R26") (pin "2") (pinfunction "2_2") (pintype "passive"))
    )
    (net (code "24") (name "Net-(CMRR_AC-Pad1)") (class "Default")
      (node (ref "CMRR_AC") (pin "1") (pinfunction "1_1") (pintype "passive"))
      (node (ref "RAB_1") (pin "1") (pinfunction "1_1") (pintype "passive"))
    )
    (net (code "25") (name "Net-(CMRR_AC-Pad2)") (class "Default")
      (node (ref "CMRR_AC") (pin "2") (pinfunction "2_2") (pintype "passive"))
      (node (ref "RAB_2") (pin "2") (pinfunction "2_2") (pintype "passive"))
    )
    (net (code "26") (name "Net-(CONN3-+V-PadA4)") (class "Default")
      (node (ref "CONN3") (pin "A4") (pinfunction "+V_A4") (pintype "passive"))
      (node (ref "CONN3") (pin "A9") (pinfunction "+V_A9") (pintype "passive"))
      (node (ref "CONN3") (pin "B4") (pinfunction "+V_B4") (pintype "passive"))
      (node (ref "CONN3") (pin "B9") (pinfunction "+V_B9") (pintype "passive"))
      (node (ref "D9") (pin "K") (pinfunction "K_K") (pintype "passive"))
      (node (ref "F1") (pin "1") (pinfunction "1_1") (pintype "passive"))
      (node (ref "TP14") (pin "1") (pinfunction "1_1") (pintype "passive"))
    )
    (net (code "27") (name "Net-(CS1-ADJ)") (class "Default")
      (node (ref "CS1") (pin "1") (pinfunction "ADJ_1") (pintype "passive"))
      (node (ref "RS1") (pin "1") (pinfunction "1_1") (pintype "passive"))
    )
    (net (code "28") (name "Net-(CS1-v-)") (class "Default")
      (node (ref "CF4") (pin "2") (pinfunction "2_2") (pintype "passive"))
      (node (ref "CS1") (pin "6") (pinfunction "v-_6") (pintype "output"))
      (node (ref "RF11") (pin "1") (pinfunction "1_1") (pintype "passive"))
      (node (ref "RF11") (pin "3") (pinfunction "3_3") (pintype "passive"))
      (node (ref "RS2") (pin "1") (pinfunction "1_1") (pintype "passive"))
      (node (ref "U4") (pin "6") (pinfunction "-_6") (pintype "passive"))
      (node (ref "U7") (pin "3") (pinfunction "PD1-_3") (pintype "passive"))
    )
    (net (code "29") (name "Net-(CS2-ADJ)") (class "Default")
      (node (ref "CS2") (pin "1") (pinfunction "ADJ_1") (pintype "passive"))
      (node (ref "RS3") (pin "2") (pinfunction "2_2") (pintype "passive"))
    )
    (net (code "30") (name "Net-(CS2-v-)") (class "Default")
      (node (ref "CF5") (pin "2") (pinfunction "2_2") (pintype "passive"))
      (node (ref "CS2") (pin "6") (pinfunction "v-_6") (pintype "output"))
      (node (ref "RF12") (pin "1") (pinfunction "1_1") (pintype "passive"))
      (node (ref "RS4") (pin "1") (pinfunction "1_1") (pintype "passive"))
      (node (ref "U5") (pin "2") (pinfunction "-_2") (pintype "passive"))
      (node (ref "U7") (pin "6") (pinfunction "PD2-_6") (pintype "passive"))
    )
    (net (code "31") (name "Net-(D2-PadA)") (class "Default")
      (node (ref "D2") (pin "A") (pinfunction "A_A") (pintype "passive"))
      (node (ref "R2") (pin "1") (pinfunction "1_1") (pintype "passive"))
    )
    (net (code "32") (name "Net-(D3-PadA)") (class "Default")
      (node (ref "D3") (pin "A") (pinfunction "A_A") (pintype "passive"))
      (node (ref "L1") (pin "1") (pinfunction "1_1") (pintype "passive"))
      (node (ref "U10") (pin "1") (pinfunction "INP_1") (pintype "passive"))
      (node (ref "U10") (pin "24") (pinfunction "INP_24") (pintype "passive"))
    )
    (net (code "33") (name "Net-(D4-PadK)") (class "Default")
      (node (ref "D4") (pin "K") (pinfunction "K_K") (pintype "passive"))
      (node (ref "L2") (pin "1") (pinfunction "1_1") (pintype "passive"))
      (node (ref "U10") (pin "13") (pinfunction "OUTN_13") (pintype "passive"))
      (node (ref "U10") (pin "14") (pinfunction "OUTN_14") (pintype "passive"))
    )
    (net (code "34") (name "Net-(D5-PadA)") (class "Default")
      (node (ref "D5") (pin "A") (pinfunction "A_A") (pintype "passive"))
      (node (ref "R24") (pin "1") (pinfunction "1_1") (pintype "passive"))
    )
    (net (code "35") (name "Net-(D10-PadA)") (class "Default")
      (node (ref "D10") (pin "A") (pinfunction "A_A") (pintype "passive"))
      (node (ref "D9") (pin "A") (pinfunction "A_A") (pintype "passive"))
    )
    (net (code "36") (name "Net-(DP_1-PadA)") (class "Default")
      (node (ref "DP_1") (pin "A") (pinfunction "A_A") (pintype "passive"))
      (node (ref "DP_2") (pin "A") (pinfunction "A_A") (pintype "passive"))
    )
    (net (code "37") (name "Net-(L3-Pad1)") (class "Default")
      (node (ref "L3") (pin "1") (pinfunction "1_1") (pintype "passive"))
      (node (ref "R23") (pin "1") (pinfunction "1_1") (pintype "passive"))
    )
    (net (code "38") (name "Net-(L5-Pad1)") (class "Default")
      (node (ref "L5") (pin "1") (pinfunction "1_1") (pintype "passive"))
      (node (ref "R31") (pin "2") (pinfunction "2_2") (pintype "passive"))
    )
    (net (code "39") (name "Net-(Q1-D)") (class "Default")
      (node (ref "C18") (pin "2") (pinfunction "2_2") (pintype "passive"))
      (node (ref "L1") (pin "2") (pinfunction "2_2") (pintype "passive"))
      (node (ref "Q1") (pin "3") (pinfunction "D_3") (pintype "passive"))
    )
    (net (code "40") (name "Net-(Q1-G)") (class "Default")
      (node (ref "Q1") (pin "1") (pinfunction "G_1") (pintype "passive"))
      (node (ref "U10") (pin "7") (pinfunction "BSW_7") (pintype "passive"))
    )
    (net (code "41") (name "Net-(Q2-G)") (class "Default")
      (node (ref "D7") (pin "A") (pinfunction "A_A") (pintype "passive"))
      (node (ref "Q2") (pin "1") (pinfunction "G_1") (pintype "passive"))
      (node (ref "Q3") (pin "3") (pinfunction "D_3") (pintype "passive"))
      (node (ref "R21") (pin "2") (pinfunction "2_2") (pintype "passive"))
    )
    (net (code "42") (name "Net-(Q2-S)") (class "Default")
      (node (ref "C61") (pin "2") (pinfunction "2_2") (pintype "passive"))
      (node (ref "D7") (pin "K") (pinfunction "K_K") (pintype "passive"))
      (node (ref "FB1") (pin "1") (pinfunction "1_1") (pintype "passive"))
      (node (ref "Q2") (pin "2") (pinfunction "S_2") (pintype "passive"))
      (node (ref "Q3") (pin "2") (pinfunction "S_2") (pintype "passive"))
      (node (ref "R22") (pin "2") (pinfunction "2_2") (pintype "passive"))
      (node (ref "R26") (pin "1") (pinfunction "1_1") (pintype "passive"))
    )
    (net (code "43") (name "Net-(Q3-G)") (class "Default")
      (node (ref "D8") (pin "K") (pinfunction "K_K") (pintype "passive"))
      (node (ref "Q3") (pin "1") (pinfunction "G_1") (pintype "passive"))
      (node (ref "R22") (pin "1") (pinfunction "1_1") (pintype "passive"))
    )
    (net (code "44") (name "Net-(R6-Pad1)") (class "Default")
      (node (ref "R6") (pin "1") (pinfunction "1_1") (pintype "passive"))
      (node (ref "RPB_4") (pin "1") (pinfunction "1_1") (pintype "passive"))
    )
    (net (code "45") (name "Net-(R19-Pad1)") (class "Default")
      (node (ref "R19") (pin "1") (pinfunction "1_1") (pintype "passive"))
      (node (ref "RPB_5") (pin "2") (pinfunction "2_2") (pintype "passive"))
    )
    (net (code "46") (name "Net-(RA_1-Pad2)") (class "Default")
      (node (ref "RA_1") (pin "2") (pinfunction "2_2") (pintype "passive"))
      (node (ref "RA_2") (pin "1") (pinfunction "1_1") (pintype "passive"))
    )
    (net (code "47") (name "Net-(RA_2-Pad2)") (class "Default")
      (node (ref "RA_2") (pin "2") (pinfunction "2_2") (pintype "passive"))
      (node (ref "RA_3") (pin "1") (pinfunction "1_1") (pintype "passive"))
    )
    (net (code "48") (name "Net-(RA_4-Pad2)") (class "Default")
      (node (ref "RA_4") (pin "2") (pinfunction "2_2") (pintype "passive"))
      (node (ref "RA_5") (pin "1") (pinfunction "1_1") (pintype "passive"))
    )
    (net (code "49") (name "Net-(RB2-Pad1)") (class "Default")
      (node (ref "RB2") (pin "1") (pinfunction "1_1") (pintype "passive"))
      (node (ref "RB_4") (pin "2") (pinfunction "2_2") (pintype "passive"))
    )
    (net (code "50") (name "Net-(RB_1-Pad2)") (class "Default")
      (node (ref "RB_1") (pin "2") (pinfunction "2_2") (pintype "passive"))
      (node (ref "RB_2") (pin "1") (pinfunction "1_1") (pintype "passive"))
    )
    (net (code "51") (name "Net-(RB_2-Pad2)") (class "Default")
      (node (ref "RB_2") (pin "2") (pinfunction "2_2") (pintype "passive"))
      (node (ref "RB_3") (pin "1") (pinfunction "1_1") (pintype "passive"))
    )
    (net (code "52") (name "Net-(RF10-Pad2)") (class "Default")
      (node (ref "RF10") (pin "2") (pinfunction "2_2") (pintype "passive"))
      (node (ref "RF11") (pin "2") (pinfunction "2_2") (pintype "passive"))
    )
    (net (code "53") (name "Net-(RG1-Pad1)") (class "Default")
      (node (ref "RG1") (pin "1") (pinfunction "1_1") (pintype "passive"))
      (node (ref "U1") (pin "2") (pinfunction "RG_2") (pintype "passive"))
    )
    (net (code "54") (name "Net-(RG1-Pad2)") (class "Default")
      (node (ref "RG1") (pin "2") (pinfunction "2_2") (pintype "passive"))
      (node (ref "U1") (pin "3") (pinfunction "RG_3") (pintype "passive"))
    )
    (net (code "55") (name "Net-(RPB_1-Pad2)") (class "Default")
      (node (ref "RPB_1") (pin "2") (pinfunction "2_2") (pintype "passive"))
      (node (ref "RPB_2") (pin "1") (pinfunction "1_1") (pintype "passive"))
    )
    (net (code "56") (name "Net-(RS1-Pad2)") (class "Default")
      (node (ref "RS1") (pin "2") (pinfunction "2_2") (pintype "passive"))
      (node (ref "RS1") (pin "3") (pinfunction "3_3") (pintype "passive"))
      (node (ref "RS2") (pin "2") (pinfunction "2_2") (pintype "passive"))
    )
    (net (code "57") (name "Net-(RS3-Pad1)") (class "Default")
      (node (ref "RS3") (pin "1") (pinfunction "1_1") (pintype "passive"))
      (node (ref "RS4") (pin "2") (pinfunction "2_2") (pintype "passive"))
    )
    (net (code "58") (name "Net-(SW1A-COMM1)") (class "Default")
      (node (ref "R15") (pin "2") (pinfunction "2_2") (pintype "passive"))
      (node (ref "SW1") (pin "3") (pinfunction "COMM1_3") (pintype "passive"))
      (node (ref "U4") (pin "3") (pinfunction "+_3") (pintype "passive"))
    )
    (net (code "59") (name "Net-(SW1A-POS1)") (class "Default")
      (node (ref "RG12") (pin "2") (pinfunction "2_2") (pintype "passive"))
      (node (ref "RG13") (pin "1") (pinfunction "1_1") (pintype "passive"))
      (node (ref "SW1") (pin "1") (pinfunction "POS1_1") (pintype "passive"))
      (node (ref "SW1") (pin "2") (pinfunction "POS2_2") (pintype "passive"))
    )
    (net (code "60") (name "Net-(SW1B-COMM2)") (class "Default")
      (node (ref "R14") (pin "2") (pinfunction "2_2") (pintype "passive"))
      (node (ref "SW1") (pin "7") (pinfunction "COMM2_7") (pintype "passive"))
      (node (ref "U3") (pin "3") (pinfunction "+_3") (pintype "passive"))
    )
    (net (code "61") (name "Net-(SW1B-POS1_2)") (class "Default")
      (node (ref "RG7") (pin "2") (pinfunction "2_2") (pintype "passive"))
      (node (ref "RG8") (pin "1") (pinfunction "1_1") (pintype "passive"))
      (node (ref "SW1") (pin "5") (pinfunction "POS1_2_5") (pintype "passive"))
    )
    (net (code "62") (name "Net-(SW2A-COM1)") (class "Default")
      (node (ref "CB_1") (pin "2") (pinfunction "2_2") (pintype "passive"))
      (node (ref "CB_2") (pin "2") (pinfunction "2_2") (pintype "passive"))
      (node (ref "D1") (pin "A") (pinfunction "A_A") (pintype "passive"))
      (node (ref "RB_3") (pin "2") (pinfunction "2_2") (pintype "passive"))
      (node (ref "SW2") (pin "2") (pinfunction "COM1_2") (pintype "passive"))
      (node (ref "TP5") (pin "1") (pinfunction "1_1") (pintype "passive"))
    )
    (net (code "63") (name "Net-(SW2A-NC1)") (class "Default")
      (node (ref "CB_1") (pin "1") (pinfunction "1_1") (pintype "passive"))
      (node (ref "CB_2") (pin "1") (pinfunction "1_1") (pintype "passive"))
      (node (ref "RAB_2") (pin "1") (pinfunction "1_1") (pintype "passive"))
      (node (ref "RB_4") (pin "1") (pinfunction "1_1") (pintype "passive"))
      (node (ref "SW2") (pin "1") (pinfunction "NC1_1") (pintype "passive"))
    )
    (net (code "64") (name "Net-(SW2B-COM2)") (class "Default")
      (node (ref "CA_1") (pin "2") (pinfunction "2_2") (pintype "passive"))
      (node (ref "CA_2") (pin "2") (pinfunction "2_2") (pintype "passive"))
      (node (ref "D1") (pin "K") (pinfunction "K_K") (pintype "passive"))
      (node (ref "RA_3") (pin "2") (pinfunction "2_2") (pintype "passive"))
      (node (ref "RA_3") (pin "3") (pinfunction "3_3") (pintype "passive"))
      (node (ref "SW2") (pin "5") (pinfunction "COM2_5") (pintype "passive"))
      (node (ref "TP1") (pin "1") (pinfunction "1_1") (pintype "passive"))
    )
    (net (code "65") (name "Net-(SW2B-NC2)") (class "Default")
      (node (ref "CA_1") (pin "1") (pinfunction "1_1") (pintype "passive"))
      (node (ref "CA_2") (pin "1") (pinfunction "1_1") (pintype "passive"))
      (node (ref "RAB_1") (pin "2") (pinfunction "2_2") (pintype "passive"))
      (node (ref "RA_4") (pin "1") (pinfunction "1_1") (pintype "passive"))
      (node (ref "SW2") (pin "4") (pinfunction "NC2_4") (pintype "passive"))
    )
    (net (code "66") (name "Net-(SW3A-COMM1)") (class "Default")
      (node (ref "RPB_3") (pin "2") (pinfunction "2_2") (pintype "passive"))
      (node (ref "SW3") (pin "3") (pinfunction "COMM1_3") (pintype "passive"))
      (node (ref "TP3") (pin "1") (pinfunction "1_1") (pintype "passive"))
      (node (ref "U3") (pin "5") (pinfunction "+_5") (pintype "passive"))
    )
    (net (code "67") (name "Net-(SW3A-POS1)") (class "Default")
      (node (ref "CF_6") (pin "2") (pinfunction "2_2") (pintype "passive"))
      (node (ref "SW3") (pin "1") (pinfunction "POS1_1") (pintype "passive"))
    )
    (net (code "68") (name "Net-(SW3A-POS2)") (class "Default")
      (node (ref "CF_5") (pin "2") (pinfunction "2_2") (pintype "passive"))
      (node (ref "SW3") (pin "2") (pinfunction "POS2_2") (pintype "passive"))
    )
    (net (code "69") (name "Net-(SW3A-POS3)") (class "Default")
      (node (ref "CF_4") (pin "2") (pinfunction "2_2") (pintype "passive"))
      (node (ref "SW3") (pin "4") (pinfunction "POS3_4") (pintype "passive"))
    )
    (net (code "70") (name "Net-(SW3B-COMM2)") (class "Default")
      (node (ref "RPB_2") (pin "2") (pinfunction "2_2") (pintype "passive"))
      (node (ref "RPB_3") (pin "1") (pinfunction "1_1") (pintype "passive"))
      (node (ref "SW3") (pin "7") (pinfunction "COMM2_7") (pintype "passive"))
    )
    (net (code "71") (name "Net-(SW3B-POS1_2)") (class "Default")
      (node (ref "CF_3") (pin "2") (pinfunction "2_2") (pintype "passive"))
      (node (ref "SW3") (pin "5") (pinfunction "POS1_2_5") (pintype "passive"))
    )
    (net (code "72") (name "Net-(SW3B-POS2_2)") (class "Default")
      (node (ref "CF_2") (pin "2") (pinfunction "2_2") (pintype "passive"))
      (node (ref "SW3") (pin "6") (pinfunction "POS2_2_6") (pintype "passive"))
    )
    (net (code "73") (name "Net-(SW3B-POS3_2)") (class "Default")
      (node (ref "CF_1") (pin "2") (pinfunction "2_2") (pintype "passive"))
      (node (ref "SW3") (pin "8") (pinfunction "POS3_2_8") (pintype "passive"))
    )
    (net (code "74") (name "Net-(SW4A-COM1)") (class "Default")
      (node (ref "R1") (pin "2") (pinfunction "2_2") (pintype "passive"))
      (node (ref "SW4") (pin "2") (pinfunction "COM1_2") (pintype "passive"))
      (node (ref "SW4") (pin "5") (pinfunction "COM2_5") (pintype "passive"))
    )
    (net (code "75") (name "Net-(U1-IN+)") (class "Default")
      (node (ref "CAB1") (pin "1") (pinfunction "1_1") (pintype "passive"))
      (node (ref "DP_2") (pin "K") (pinfunction "K_K") (pintype "passive"))
      (node (ref "RB2") (pin "2") (pinfunction "2_2") (pintype "passive"))
      (node (ref "U1") (pin "4") (pinfunction "IN+_4") (pintype "tri_state"))
    )
    (net (code "76") (name "Net-(U1-IN-)") (class "Default")
      (node (ref "CAB1") (pin "2") (pinfunction "2_2") (pintype "passive"))
      (node (ref "DP_1") (pin "K") (pinfunction "K_K") (pintype "passive"))
      (node (ref "RA_5") (pin "2") (pinfunction "2_2") (pintype "passive"))
      (node (ref "RA_5") (pin "3") (pinfunction "3_3") (pintype "passive"))
      (node (ref "U1") (pin "1") (pinfunction "IN-_1") (pintype "tri_state"))
    )
    (net (code "77") (name "Net-(U1-Out)") (class "Default")
      (node (ref "RPB_1") (pin "1") (pinfunction "1_1") (pintype "passive"))
      (node (ref "TP2") (pin "1") (pinfunction "1_1") (pintype "passive"))
      (node (ref "U1") (pin "7") (pinfunction "Out_7") (pintype "output"))
    )
    (net (code "78") (name "Net-(U2A-+)") (class "Default")
      (node (ref "U2") (pin "3") (pinfunction "+_3") (pintype "passive"))
      (node (ref "U2") (pin "6") (pinfunction "-_6") (pintype "passive"))
      (node (ref "U2") (pin "7") (pinfunction "OUT_7") (pintype "output"))
    )
    (net (code "79") (name "Net-(U2A--)") (class "Default")
      (node (ref "CF1") (pin "2") (pinfunction "2_2") (pintype "passive"))
      (node (ref "RF1") (pin "2") (pinfunction "2_2") (pintype "passive"))
      (node (ref "RF2") (pin "1") (pinfunction "1_1") (pintype "passive"))
      (node (ref "RF3") (pin "1") (pinfunction "1_1") (pintype "passive"))
      (node (ref "U2") (pin "2") (pinfunction "-_2") (pintype "passive"))
    )
    (net (code "80") (name "Net-(U2A-OUT)") (class "Default")
      (node (ref "R8") (pin "1") (pinfunction "1_1") (pintype "passive"))
      (node (ref "U2") (pin "1") (pinfunction "OUT_1") (pintype "output"))
    )
    (net (code "81") (name "Net-(U3A--)") (class "Default")
      (node (ref "CF2") (pin "1") (pinfunction "1_1") (pintype "passive"))
      (node (ref "RF4") (pin "1") (pinfunction "1_1") (pintype "passive"))
      (node (ref "RF5") (pin "1") (pinfunction "1_1") (pintype "passive"))
      (node (ref "RF6") (pin "1") (pinfunction "1_1") (pintype "passive"))
      (node (ref "U3") (pin "2") (pinfunction "-_2") (pintype "passive"))
    )
    (net (code "82") (name "Net-(U3A-OUT)") (class "Default")
      (node (ref "CF2") (pin "2") (pinfunction "2_2") (pintype "passive"))
      (node (ref "R15") (pin "1") (pinfunction "1_1") (pintype "passive"))
      (node (ref "RF4") (pin "2") (pinfunction "2_2") (pintype "passive"))
      (node (ref "TP23") (pin "1") (pinfunction "1_1") (pintype "passive"))
      (node (ref "U3") (pin "1") (pinfunction "OUT_1") (pintype "output"))
    )
    (net (code "83") (name "Net-(U3B--)") (class "Default")
      (node (ref "R14") (pin "1") (pinfunction "1_1") (pintype "passive"))
      (node (ref "U3") (pin "6") (pinfunction "-_6") (pintype "passive"))
      (node (ref "U3") (pin "7") (pinfunction "OUT_7") (pintype "output"))
    )
    (net (code "84") (name "Net-(U4A--)") (class "Default")
      (node (ref "CF3") (pin "1") (pinfunction "1_1") (pintype "passive"))
      (node (ref "RF7") (pin "1") (pinfunction "1_1") (pintype "passive"))
      (node (ref "RF8") (pin "1") (pinfunction "1_1") (pintype "passive"))
      (node (ref "RF9") (pin "1") (pinfunction "1_1") (pintype "passive"))
      (node (ref "U4") (pin "2") (pinfunction "-_2") (pintype "passive"))
    )
    (net (code "85") (name "Net-(U4A-OUT)") (class "Default")
      (node (ref "CF3") (pin "2") (pinfunction "2_2") (pintype "passive"))
      (node (ref "RF10") (pin "1") (pinfunction "1_1") (pintype "passive"))
      (node (ref "RF7") (pin "2") (pinfunction "2_2") (pintype "passive"))
      (node (ref "TP4") (pin "1") (pinfunction "1_1") (pintype "passive"))
      (node (ref "U4") (pin "1") (pinfunction "OUT_1") (pintype "output"))
    )
    (net (code "86") (name "Net-(U4B-OUT)") (class "Default")
      (node (ref "CF4") (pin "1") (pinfunction "1_1") (pintype "passive"))
      (node (ref "RG4") (pin "1") (pinfunction "1_1") (pintype "passive"))
      (node (ref "U4") (pin "7") (pinfunction "OUT_7") (pintype "output"))
    )
    (net (code "87") (name "Net-(U5A-OUT)") (class "Default")
      (node (ref "CF5") (pin "1") (pinfunction "1_1") (pintype "passive"))
      (node (ref "RF12") (pin "2") (pinfunction "2_2") (pintype "passive"))
      (node (ref "U5") (pin "1") (pinfunction "OUT_1") (pintype "output"))
      (node (ref "U5") (pin "5") (pinfunction "+_5") (pintype "passive"))
    )
    (net (code "88") (name "Net-(U5B--)") (class "Default")
      (node (ref "R4") (pin "1") (pinfunction "1_1") (pintype "passive"))
      (node (ref "U5") (pin "6") (pinfunction "-_6") (pintype "passive"))
      (node (ref "U5") (pin "7") (pinfunction "OUT_7") (pintype "output"))
    )
    (net (code "89") (name "Net-(U7-LED-)") (class "Default")
      (node (ref "RG4") (pin "2") (pinfunction "2_2") (pintype "passive"))
      (node (ref "U7") (pin "1") (pinfunction "LED-_1") (pintype "passive"))
    )
    (net (code "90") (name "Net-(U10-CN)") (class "Default")
      (node (ref "C33") (pin "2") (pinfunction "2_2") (pintype "passive"))
      (node (ref "U10") (pin "18") (pinfunction "CN_18") (pintype "passive"))
    )
    (net (code "91") (name "Net-(U10-CP)") (class "Default")
      (node (ref "C32") (pin "2") (pinfunction "2_2") (pintype "passive"))
      (node (ref "U10") (pin "21") (pinfunction "CP_21") (pintype "passive"))
    )
    (net (code "92") (name "Net-(U10-ENN)") (class "Default")
      (node (ref "C29") (pin "2") (pinfunction "2_2") (pintype "passive"))
      (node (ref "R16") (pin "2") (pinfunction "2_2") (pintype "passive"))
      (node (ref "U10") (pin "10") (pinfunction "ENN_10") (pintype "passive"))
      (node (ref "U10") (pin "11") (pinfunction "PSN_11") (pintype "passive"))
      (node (ref "U10") (pin "4") (pinfunction "VIN_4") (pintype "passive"))
      (node (ref "U10") (pin "8") (pinfunction "ENP_8") (pintype "passive"))
      (node (ref "U10") (pin "9") (pinfunction "PSP_9") (pintype "passive"))
    )
    (net (code "93") (name "Net-(U10-FBN)") (class "Default")
      (node (ref "C27") (pin "1") (pinfunction "1_1") (pintype "passive"))
      (node (ref "R17") (pin "2") (pinfunction "2_2") (pintype "passive"))
      (node (ref "R25") (pin "1") (pinfunction "1_1") (pintype "passive"))
      (node (ref "U10") (pin "16") (pinfunction "FBN_16") (pintype "passive"))
    )
    (net (code "94") (name "Net-(U10-FBP)") (class "Default")
      (node (ref "C19") (pin "2") (pinfunction "2_2") (pintype "passive"))
      (node (ref "R11") (pin "2") (pinfunction "2_2") (pintype "passive"))
      (node (ref "R13") (pin "2") (pinfunction "2_2") (pintype "passive"))
      (node (ref "U10") (pin "22") (pinfunction "FBP_22") (pintype "passive"))
    )
    (net (code "95") (name "Net-(U10-VREF)") (class "Default")
      (node (ref "C25") (pin "2") (pinfunction "2_2") (pintype "passive"))
      (node (ref "R25") (pin "2") (pinfunction "2_2") (pintype "passive"))
      (node (ref "U10") (pin "17") (pinfunction "VREF_17") (pintype "passive"))
    )
    (net (code "96") (name "Net-(U11-FB)") (class "Default")
      (node (ref "C30") (pin "1") (pinfunction "1_1") (pintype "passive"))
      (node (ref "R19") (pin "2") (pinfunction "2_2") (pintype "passive"))
      (node (ref "R20") (pin "1") (pinfunction "1_1") (pintype "passive"))
      (node (ref "U11") (pin "2") (pinfunction "FB_2") (pintype "passive"))
    )
    (net (code "97") (name "Net-(U11-NR{slash}SS)") (class "Default")
      (node (ref "C36") (pin "1") (pinfunction "1_1") (pintype "passive"))
      (node (ref "U11") (pin "6") (pinfunction "NR/SS_6") (pintype "passive"))
    )
    (net (code "98") (name "Net-(U12-Vin)") (class "Default")
      (node (ref "C51") (pin "1") (pinfunction "1_1") (pintype "passive"))
      (node (ref "C53") (pin "1") (pinfunction "1_1") (pintype "passive"))
      (node (ref "L3") (pin "2") (pinfunction "2_2") (pintype "passive"))
      (node (ref "TP16") (pin "1") (pinfunction "1_1") (pintype "passive"))
      (node (ref "U12") (pin "1") (pinfunction "Vin_1") (pintype "passive"))
    )
    (net (code "99") (name "Net-(U13-+Vin)") (class "Default")
      (node (ref "C37") (pin "2") (pinfunction "2_2") (pintype "passive"))
      (node (ref "L4") (pin "2") (pinfunction "2_2") (pintype "passive"))
      (node (ref "U13") (pin "2") (pinfunction "+Vin_2") (pintype "passive"))
    )
    (net (code "100") (name "Net-(U13-+Vout)") (class "Default")
      (node (ref "C42") (pin "2") (pinfunction "2_2") (pintype "passive"))
      (node (ref "R23") (pin "2") (pinfunction "2_2") (pintype "passive"))
      (node (ref "U13") (pin "8") (pinfunction "+Vout_8") (pintype "power_in"))
    )
    (net (code "101") (name "Net-(U13--Vout)") (class "Default")
      (node (ref "C46") (pin "1") (pinfunction "1_1") (pintype "passive"))
      (node (ref "R31") (pin "1") (pinfunction "1_1") (pintype "passive"))
      (node (ref "U13") (pin "6") (pinfunction "-Vout_6") (pintype "passive"))
    )
    (net (code "102") (name "Net-(U16-EN)") (class "Default")
      (node (ref "C52") (pin "2") (pinfunction "2_2") (pintype "passive"))
      (node (ref "C54") (pin "2") (pinfunction "2_2") (pintype "passive"))
      (node (ref "L5") (pin "2") (pinfunction "2_2") (pintype "passive"))
      (node (ref "TP22") (pin "1") (pinfunction "1_1") (pintype "passive"))
      (node (ref "U16") (pin "5") (pinfunction "EN_5") (pintype "input"))
      (node (ref "U16") (pin "8") (pinfunction "Vin_8") (pintype "input"))
    )
    (net (code "103") (name "Net-(U16-FB)") (class "Default")
      (node (ref "C48") (pin "1") (pinfunction "1_1") (pintype "passive"))
      (node (ref "R12") (pin "1") (pinfunction "1_1") (pintype "passive"))
      (node (ref "R6") (pin "2") (pinfunction "2_2") (pintype "passive"))
      (node (ref "U16") (pin "2") (pinfunction "FB_2") (pintype "passive"))
    )
    (net (code "104") (name "Net-(U16-NR{slash}SS)") (class "Default")
      (node (ref "C49") (pin "2") (pinfunction "2_2") (pintype "passive"))
      (node (ref "U16") (pin "6") (pinfunction "NR/SS_6") (pintype "passive"))
    )
    (net (code "105") (name "Vcc_iso") (class "Default")
      (node (ref "C1") (pin "2") (pinfunction "2_2") (pintype "passive"))
      (node (ref "C14") (pin "2") (pinfunction "2_2") (pintype "passive"))
      (node (ref "C39") (pin "1") (pinfunction "1_1") (pintype "passive"))
      (node (ref "C47") (pin "1") (pinfunction "1_1") (pintype "passive"))
      (node (ref "C5") (pin "2") (pinfunction "2_2") (pintype "passive"))
      (node (ref "C58") (pin "2") (pinfunction "2_2") (pintype "passive"))
      (node (ref "CS1") (pin "4") (pinfunction "Vi+_4") (pintype "power_in"))
      (node (ref "R24") (pin "2") (pinfunction "2_2") (pintype "passive"))
      (node (ref "RG5") (pin "2") (pinfunction "2_2") (pintype "passive"))
      (node (ref "TP18") (pin "1") (pinfunction "1_1") (pintype "passive"))
      (node (ref "U1") (pin "8") (pinfunction "Vcc_8") (pintype "power_in"))
      (node (ref "U12") (pin "5") (pinfunction "Vout_5") (pintype "power_in"))
      (node (ref "U2") (pin "8") (pinfunction "VCC_8") (pintype "power_in"))
      (node (ref "U3") (pin "8") (pinfunction "VCC_8") (pintype "power_in"))
      (node (ref "U4") (pin "8") (pinfunction "VCC_8") (pintype "power_in"))
    )
    (net (code "106") (name "Vee_iso") (class "Default")
      (node (ref "C10") (pin "2") (pinfunction "2_2") (pintype "passive"))
      (node (ref "C16") (pin "2") (pinfunction "2_2") (pintype "passive"))
      (node (ref "C38") (pin "2") (pinfunction "2_2") (pintype "passive"))
      (node (ref "C41") (pin "2") (pinfunction "2_2") (pintype "passive"))
      (node (ref "C48") (pin "2") (pinfunction "2_2") (pintype "passive"))
      (node (ref "C59") (pin "2") (pinfunction "2_2") (pintype "passive"))
      (node (ref "C7") (pin "2") (pinfunction "2_2") (pintype "passive"))
      (node (ref "R12") (pin "2") (pinfunction "2_2") (pintype "passive"))
      (node (ref "RG6") (pin "2") (pinfunction "2_2") (pintype "passive"))
      (node (ref "TP20") (pin "1") (pinfunction "1_1") (pintype "passive"))
      (node (ref "U1") (pin "5") (pinfunction "Vee_5") (pintype "power_in"))
      (node (ref "U16") (pin "1") (pinfunction "Vout_1") (pintype "power_in"))
      (node (ref "U2") (pin "4") (pinfunction "GND_4") (pintype "power_in"))
      (node (ref "U3") (pin "4") (pinfunction "GND_4") (pintype "power_in"))
      (node (ref "U4") (pin "4") (pinfunction "GND_4") (pintype "power_in"))
    )
    (net (code "107") (name "unconnected-(CONN3-CC1-PadA5)") (class "Default")
      (node (ref "CONN3") (pin "A5") (pinfunction "CC1_A5") (pintype "passive+no_connect"))
    )
    (net (code "108") (name "unconnected-(CONN3-CC2-PadB5)") (class "Default")
      (node (ref "CONN3") (pin "B5") (pinfunction "CC2_B5") (pintype "passive+no_connect"))
    )
    (net (code "109") (name "unconnected-(CONN3-D+-PadA6)") (class "Default")
      (node (ref "CONN3") (pin "A6") (pinfunction "D+_A6") (pintype "passive+no_connect"))
    )
    (net (code "110") (name "unconnected-(CONN3-D+-PadB6)") (class "Default")
      (node (ref "CONN3") (pin "B6") (pinfunction "D+_B6") (pintype "passive+no_connect"))
    )
    (net (code "111") (name "unconnected-(CONN3-D--PadA7)") (class "Default")
      (node (ref "CONN3") (pin "A7") (pinfunction "D-_A7") (pintype "passive+no_connect"))
    )
    (net (code "112") (name "unconnected-(CONN3-D--PadB7)") (class "Default")
      (node (ref "CONN3") (pin "B7") (pinfunction "D-_B7") (pintype "passive+no_connect"))
    )
    (net (code "113") (name "unconnected-(CONN3-RX1+-PadB11)") (class "Default")
      (node (ref "CONN3") (pin "B11") (pinfunction "RX1+_B11") (pintype "passive+no_connect"))
    )
    (net (code "114") (name "unconnected-(CONN3-RX1--PadB10)") (class "Default")
      (node (ref "CONN3") (pin "B10") (pinfunction "RX1-_B10") (pintype "passive+no_connect"))
    )
    (net (code "115") (name "unconnected-(CONN3-RX2+-PadA11)") (class "Default")
      (node (ref "CONN3") (pin "A11") (pinfunction "RX2+_A11") (pintype "passive+no_connect"))
    )
    (net (code "116") (name "unconnected-(CONN3-RX2--PadA10)") (class "Default")
      (node (ref "CONN3") (pin "A10") (pinfunction "RX2-_A10") (pintype "passive+no_connect"))
    )
    (net (code "117") (name "unconnected-(CONN3-SBU1-PadA8)") (class "Default")
      (node (ref "CONN3") (pin "A8") (pinfunction "SBU1_A8") (pintype "passive+no_connect"))
    )
    (net (code "118") (name "unconnected-(CONN3-SBU2-PadB8)") (class "Default")
      (node (ref "CONN3") (pin "B8") (pinfunction "SBU2_B8") (pintype "passive+no_connect"))
    )
    (net (code "119") (name "unconnected-(CONN3-TX1+-PadA2)") (class "Default")
      (node (ref "CONN3") (pin "A2") (pinfunction "TX1+_A2") (pintype "passive+no_connect"))
    )
    (net (code "120") (name "unconnected-(CONN3-TX1--PadA3)") (class "Default")
      (node (ref "CONN3") (pin "A3") (pinfunction "TX1-_A3") (pintype "passive+no_connect"))
    )
    (net (code "121") (name "unconnected-(CONN3-TX2+-PadB2)") (class "Default")
      (node (ref "CONN3") (pin "B2") (pinfunction "TX2+_B2") (pintype "passive+no_connect"))
    )
    (net (code "122") (name "unconnected-(CONN3-TX2--PadB3)") (class "Default")
      (node (ref "CONN3") (pin "B3") (pinfunction "TX2-_B3") (pintype "passive+no_connect"))
    )
    (net (code "123") (name "unconnected-(FID1-Pad5)") (class "Default")
      (node (ref "FID1") (pin "5") (pinfunction "5_5") (pintype "passive"))
    )
    (net (code "124") (name "unconnected-(FID2-Pad5)") (class "Default")
      (node (ref "FID2") (pin "5") (pinfunction "5_5") (pintype "passive"))
    )
    (net (code "125") (name "unconnected-(FID3-Pad5)") (class "Default")
      (node (ref "FID3") (pin "5") (pinfunction "5_5") (pintype "passive"))
    )
    (net (code "126") (name "unconnected-(MS1-Pad5)") (class "Default")
      (node (ref "MS1") (pin "5") (pinfunction "5_5") (pintype "passive"))
    )
    (net (code "127") (name "unconnected-(MS2-Pad5)") (class "Default")
      (node (ref "MS2") (pin "5") (pinfunction "5_5") (pintype "passive"))
    )
    (net (code "128") (name "unconnected-(MS3-Pad5)") (class "Default")
      (node (ref "MS3") (pin "5") (pinfunction "5_5") (pintype "passive"))
    )
    (net (code "129") (name "unconnected-(MS4-Pad5)") (class "Default")
      (node (ref "MS4") (pin "5") (pinfunction "5_5") (pintype "passive"))
    )
    (net (code "130") (name "unconnected-(SW1A-POS3-Pad4)") (class "Default")
      (node (ref "SW1") (pin "4") (pinfunction "POS3_4") (pintype "passive+no_connect"))
    )
    (net (code "131") (name "unconnected-(SW1B-POS2_2-Pad6)") (class "Default")
      (node (ref "SW1") (pin "6") (pinfunction "POS2_2_6") (pintype "passive+no_connect"))
    )
    (net (code "132") (name "unconnected-(SW1B-POS3_2-Pad8)") (class "Default")
      (node (ref "SW1") (pin "8") (pinfunction "POS3_2_8") (pintype "passive+no_connect"))
    )
    (net (code "133") (name "unconnected-(SW2A-NO1-Pad3)") (class "Default")
      (node (ref "SW2") (pin "3") (pinfunction "NO1_3") (pintype "passive+no_connect"))
    )
    (net (code "134") (name "unconnected-(SW2B-NO2-Pad6)") (class "Default")
      (node (ref "SW2") (pin "6") (pinfunction "NO2_6") (pintype "passive+no_connect"))
    )
    (net (code "135") (name "unconnected-(U7-NC-Pad7)") (class "Default")
      (node (ref "U7") (pin "7") (pinfunction "NC_7") (pintype "passive"))
    )
    (net (code "136") (name "unconnected-(U7-NC-Pad8)") (class "Default")
      (node (ref "U7") (pin "8") (pinfunction "NC_8") (pintype "passive"))
    )
    (net (code "137") (name "unconnected-(U9-NC-Pad3)") (class "Default")
      (node (ref "U9") (pin "3") (pinfunction "NC_3") (pintype "passive+no_connect"))
    )
    (net (code "138") (name "unconnected-(U9-NC-Pad4)") (class "Default")
      (node (ref "U9") (pin "4") (pinfunction "NC_4") (pintype "passive+no_connect"))
    )
    (net (code "139") (name "unconnected-(U10-NC-Pad12)") (class "Default")
      (node (ref "U10") (pin "12") (pinfunction "NC_12") (pintype "passive"))
    )
    (net (code "140") (name "unconnected-(U10-NC-Pad20)") (class "Default")
      (node (ref "U10") (pin "20") (pinfunction "NC_20") (pintype "passive+no_connect"))
    )
    (net (code "141") (name "unconnected-(U11-NC-Pad6)") (class "Default")
      (node (ref "U11") (pin "6") (pinfunction "NC_6") (pintype "passive+no_connect"))
    )
    (net (code "142") (name "unconnected-(U12-NC-Pad3)") (class "Default")
      (node (ref "U12") (pin "3") (pinfunction "NC_3") (pintype "passive+no_connect"))
    )
    (net (code "143") (name "unconnected-(U12-NC-Pad4)") (class "Default")
      (node (ref "U12") (pin "4") (pinfunction "NC_4") (pintype "passive+no_connect"))
    )
    (net (code "144") (name "unconnected-(U16-NC-Pad6)") (class "Default")
      (node (ref "U16") (pin "6") (pinfunction "NC_6") (pintype "passive+no_connect"))
    )
  )
)
